# ALog-BottleLogger.net
KiCad netlist of a schematic drawn in EAGLE
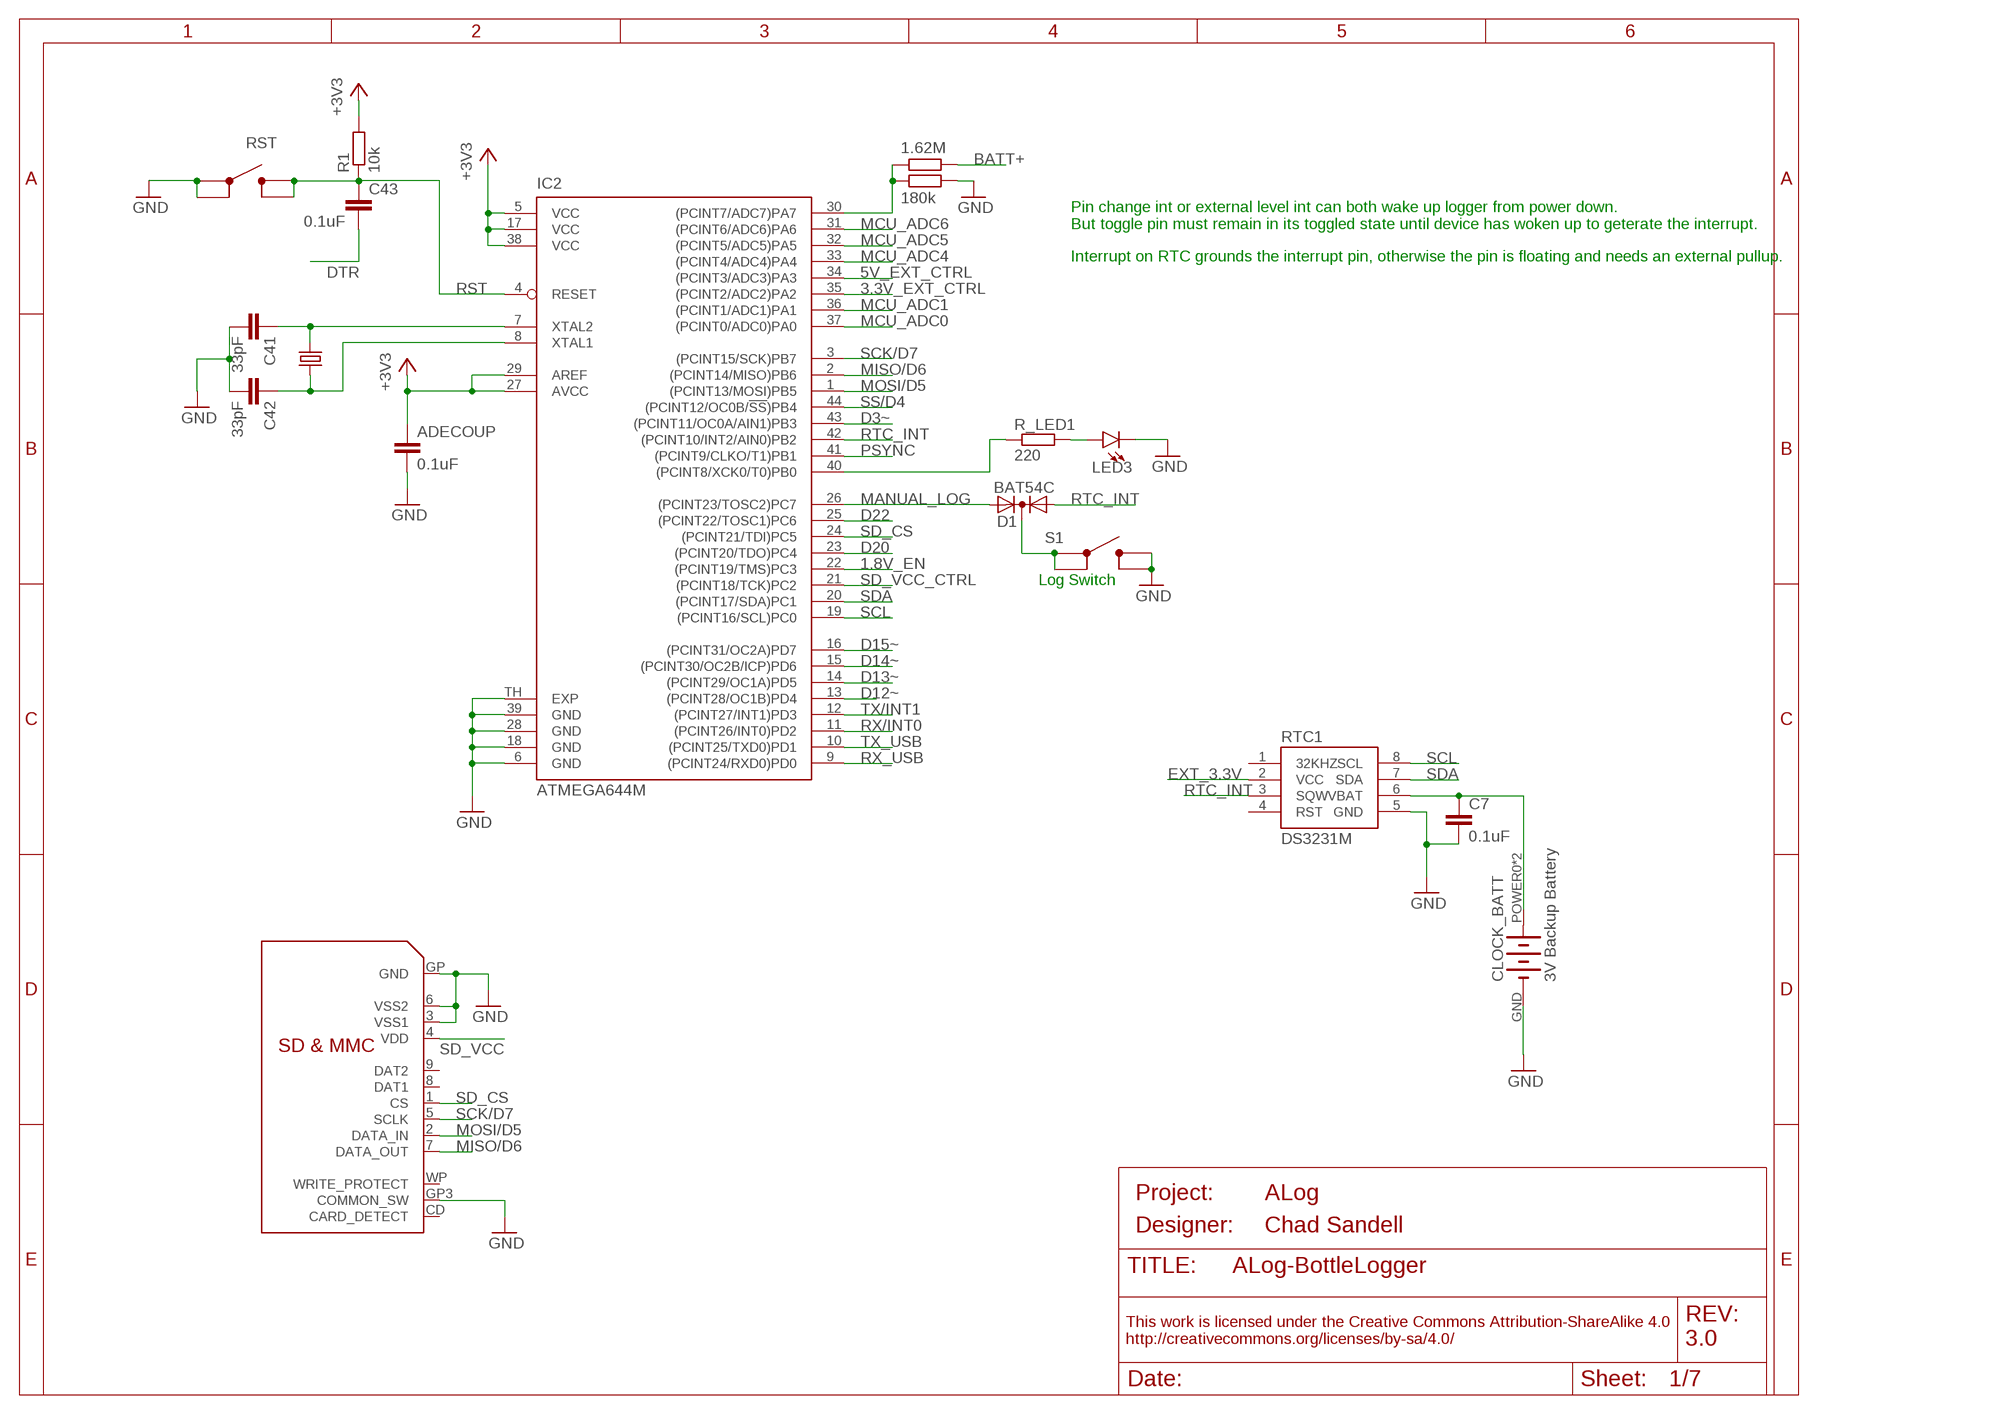
[diagram p0: schematic, sheet 1]
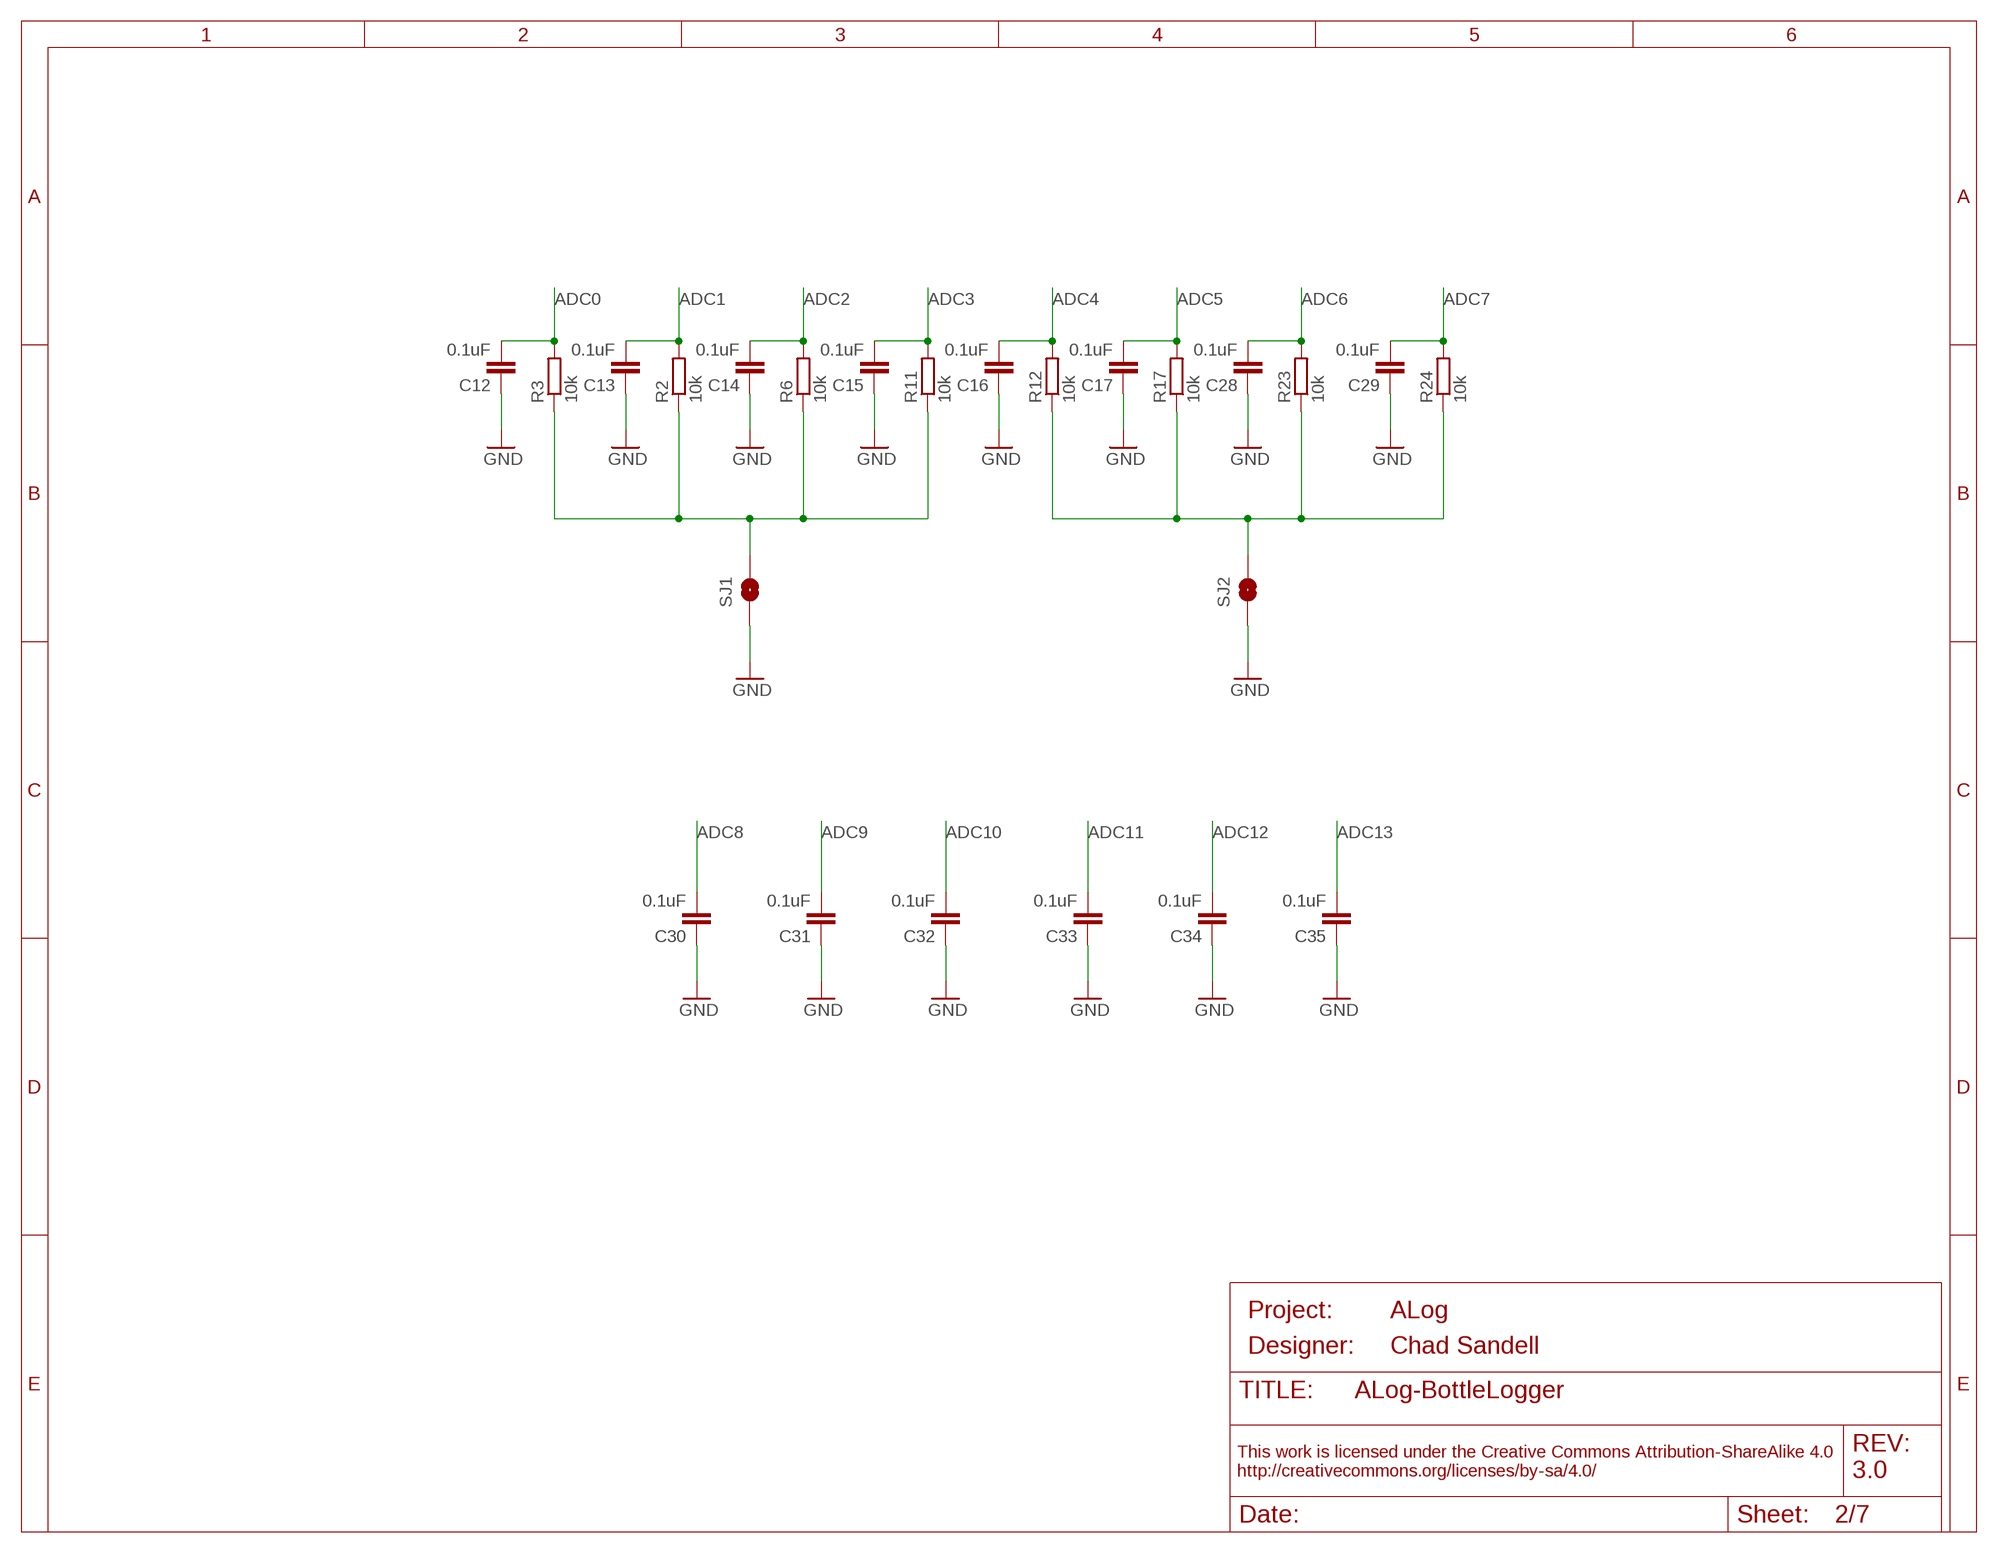
[diagram p1: schematic, sheet 2]
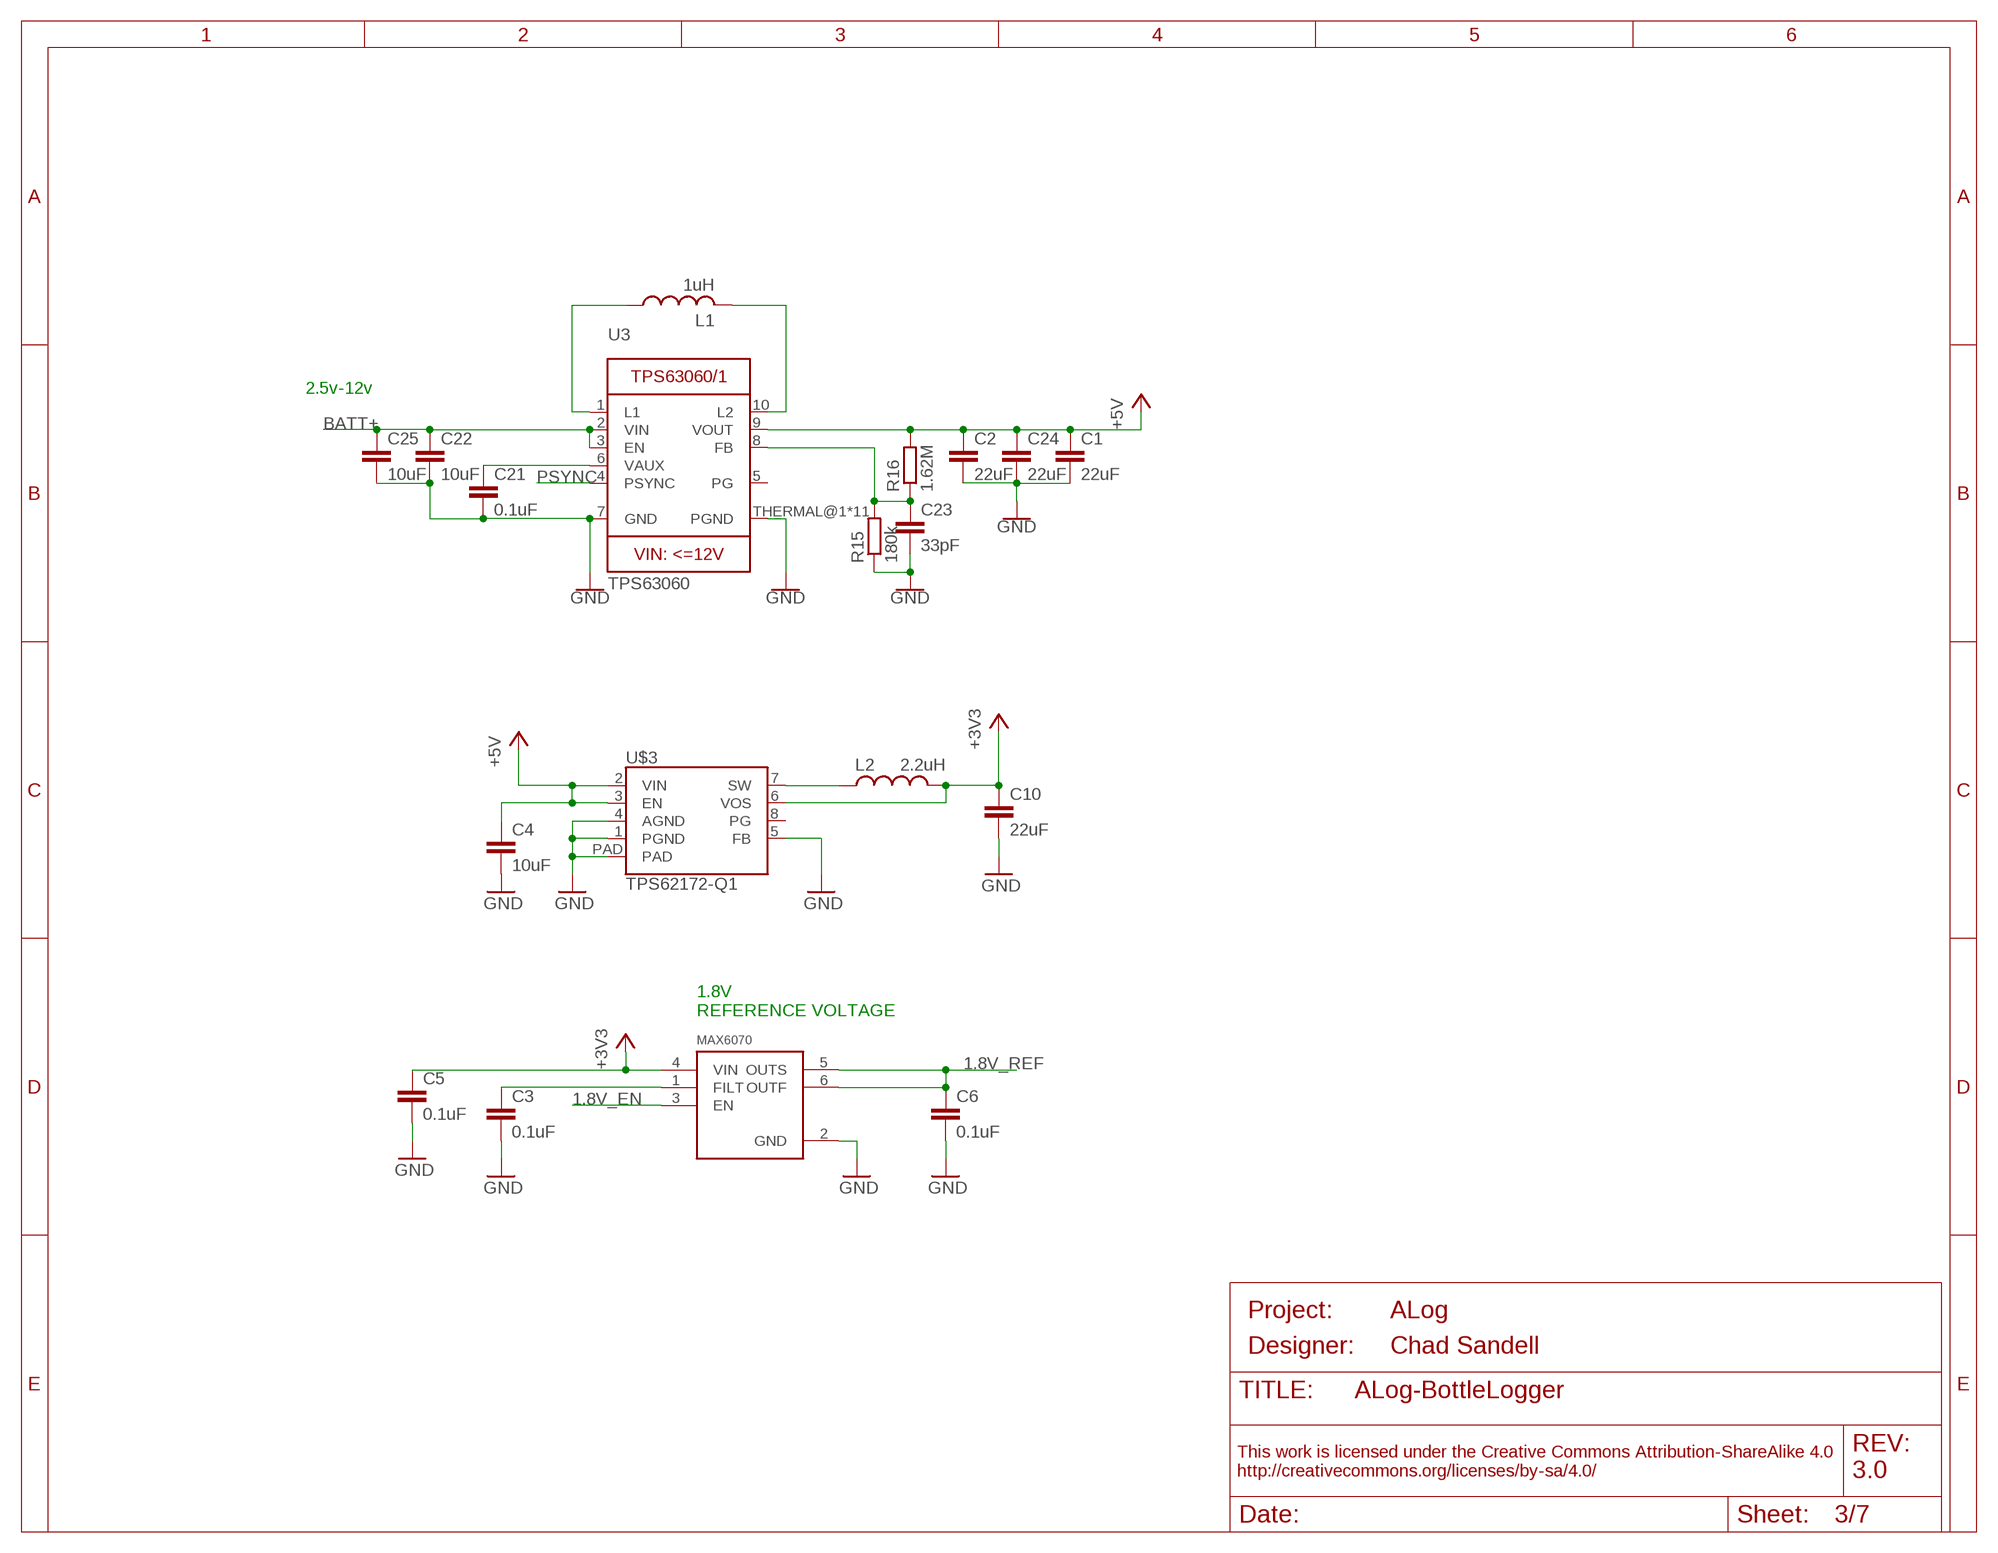
[diagram p2: schematic, sheet 3]
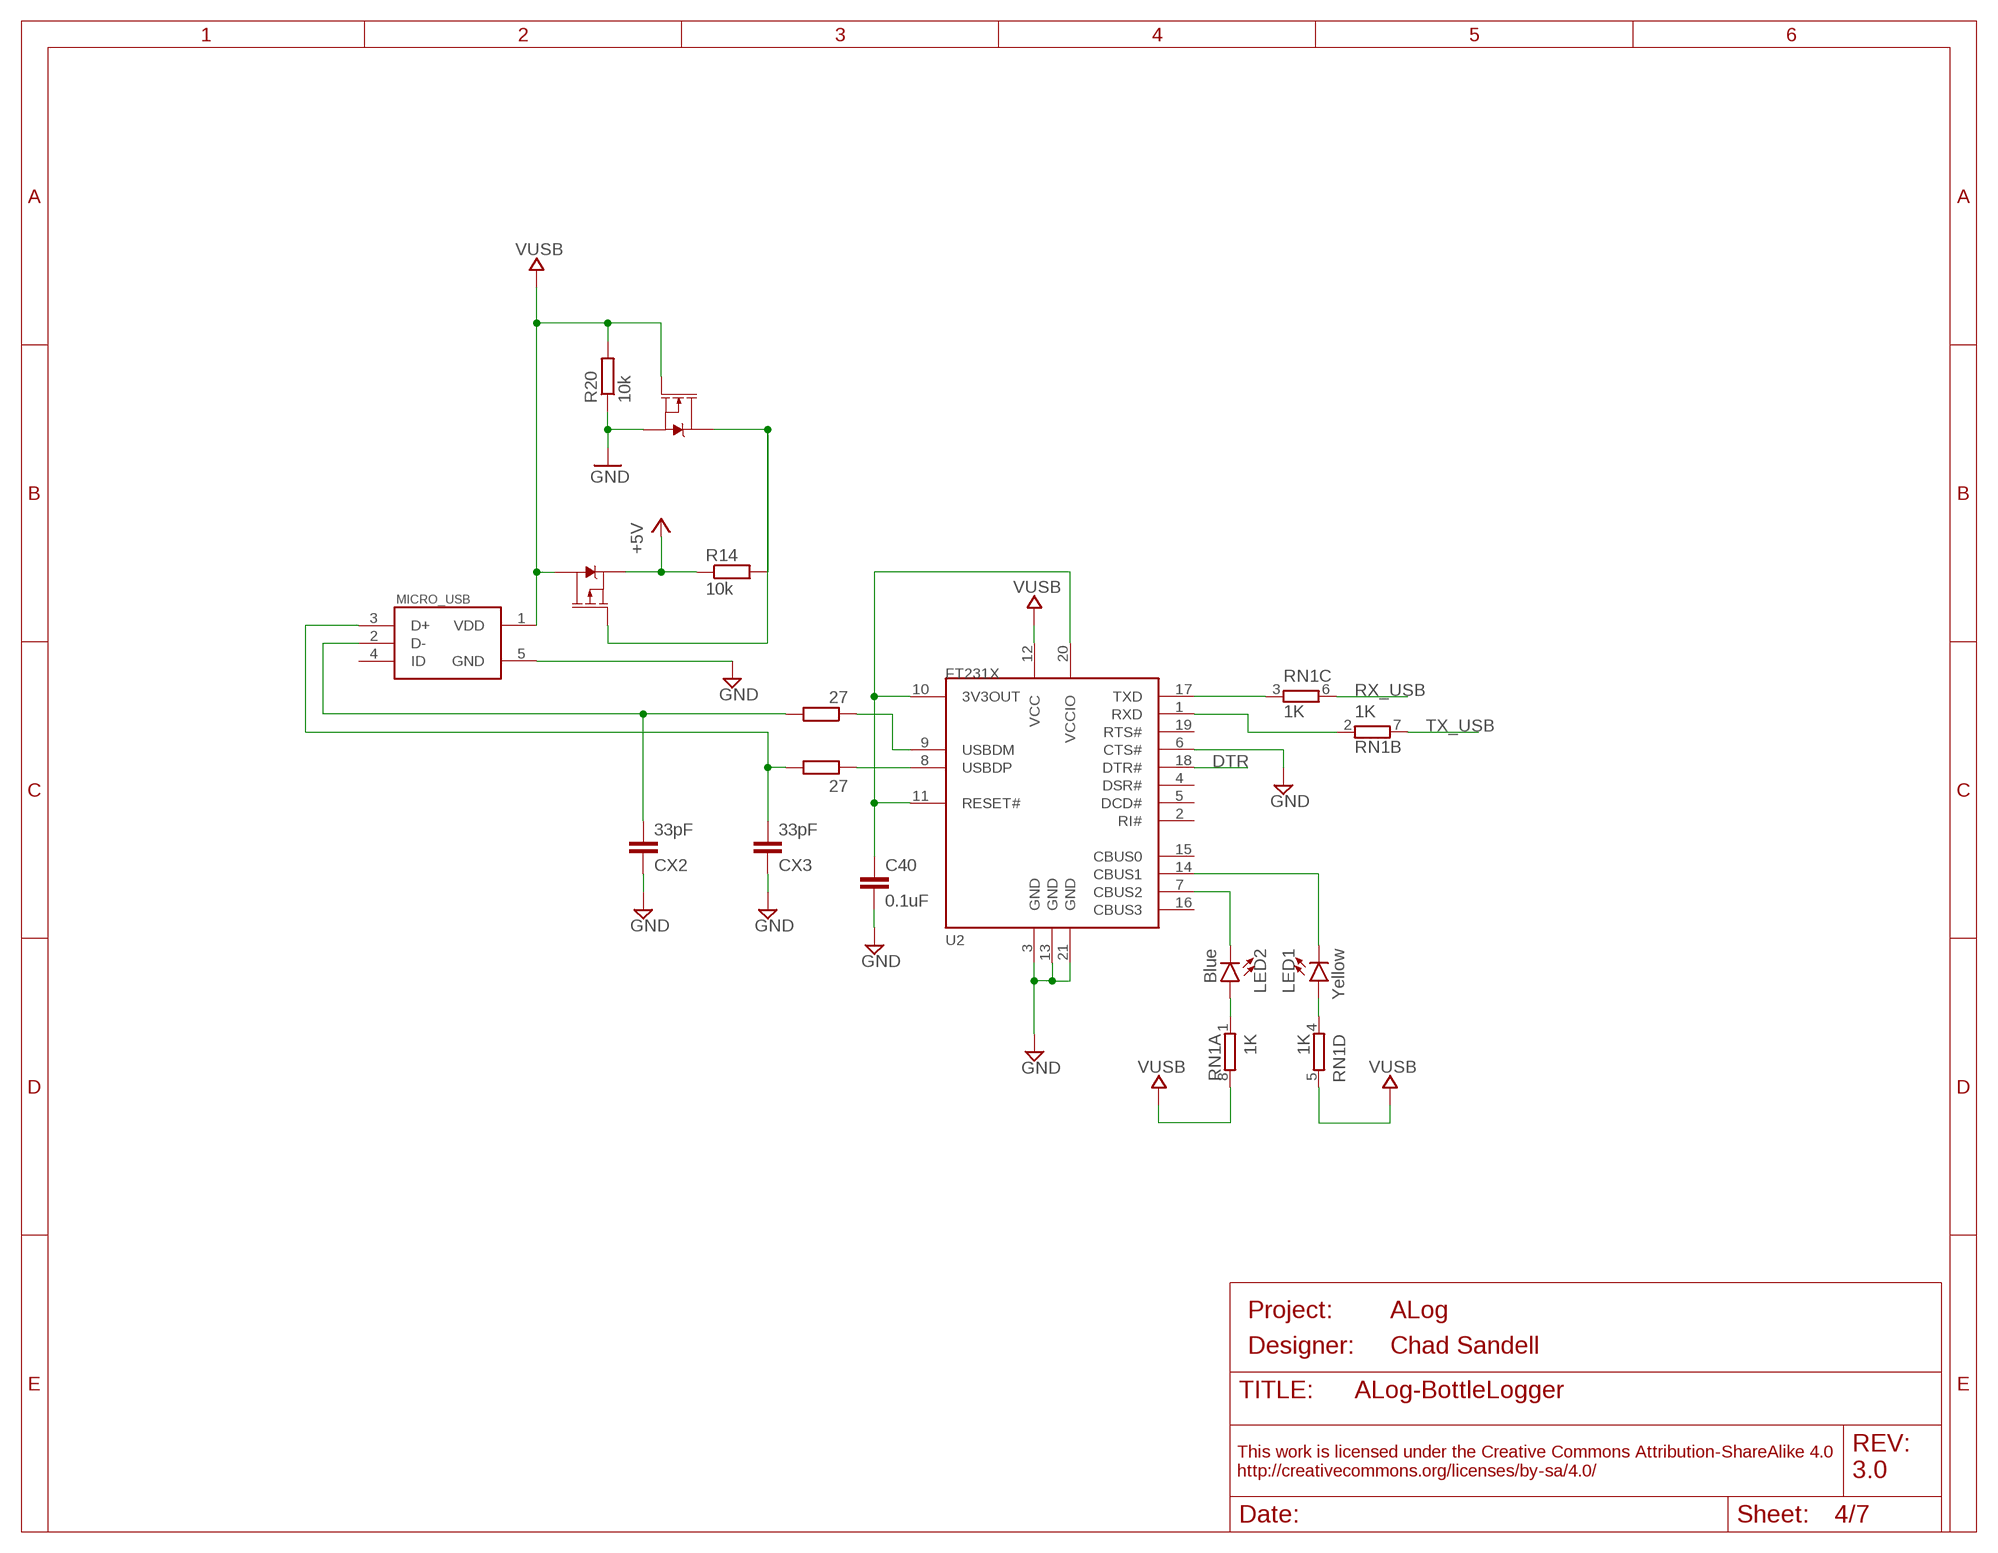
[diagram p3: schematic, sheet 4]
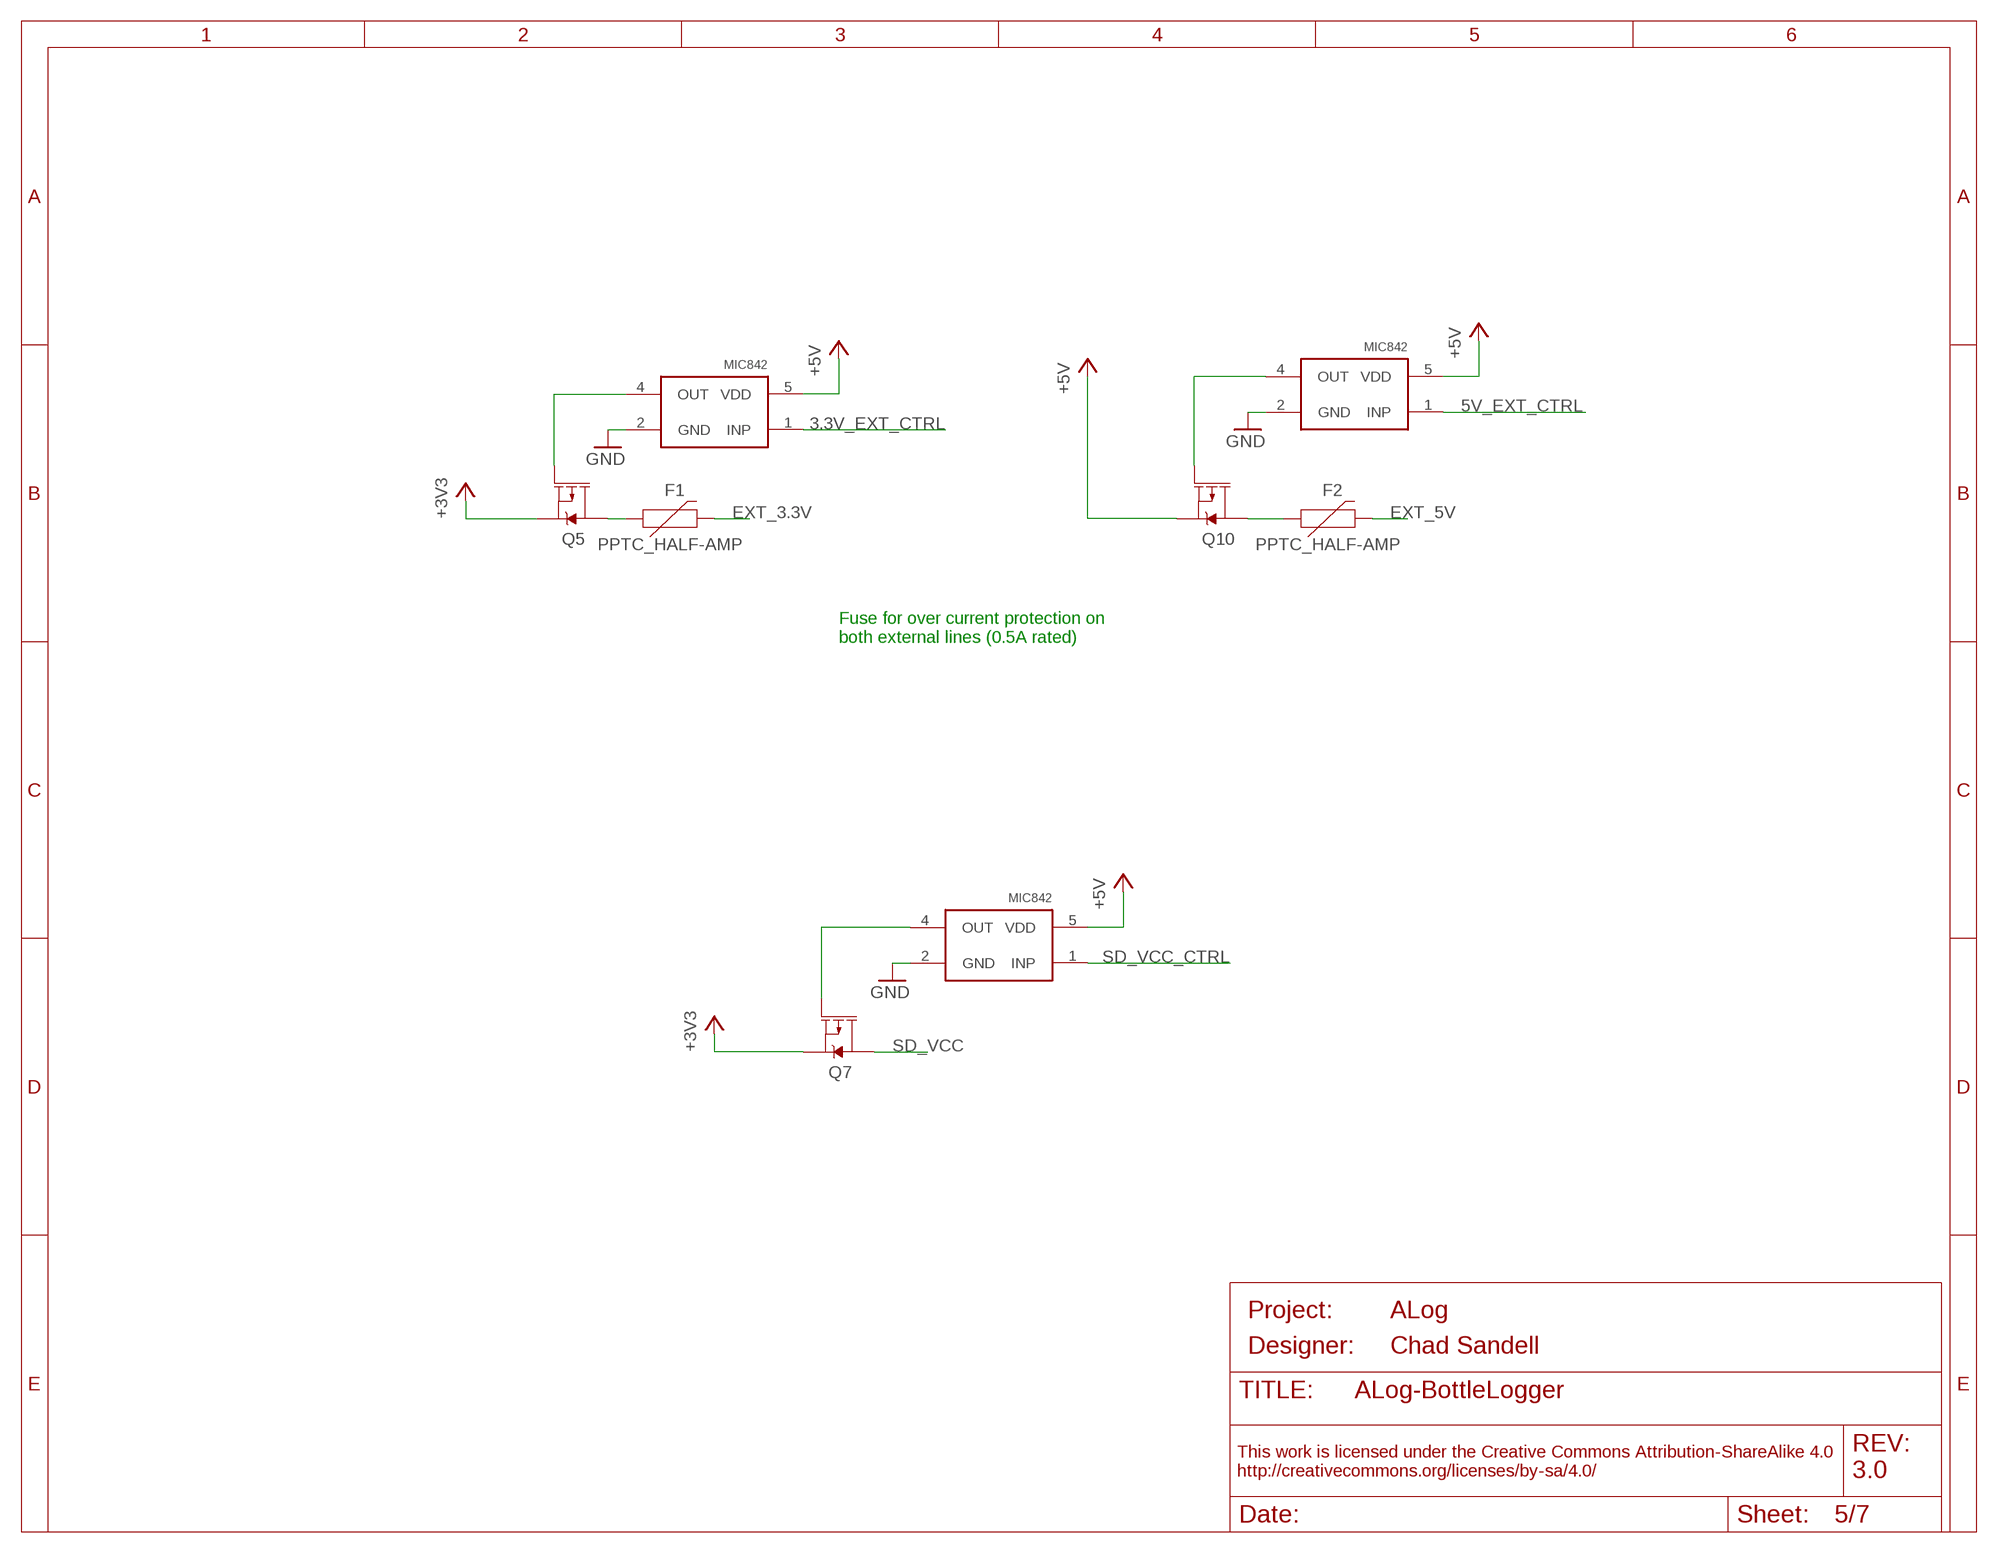
[diagram p4: schematic, sheet 5]
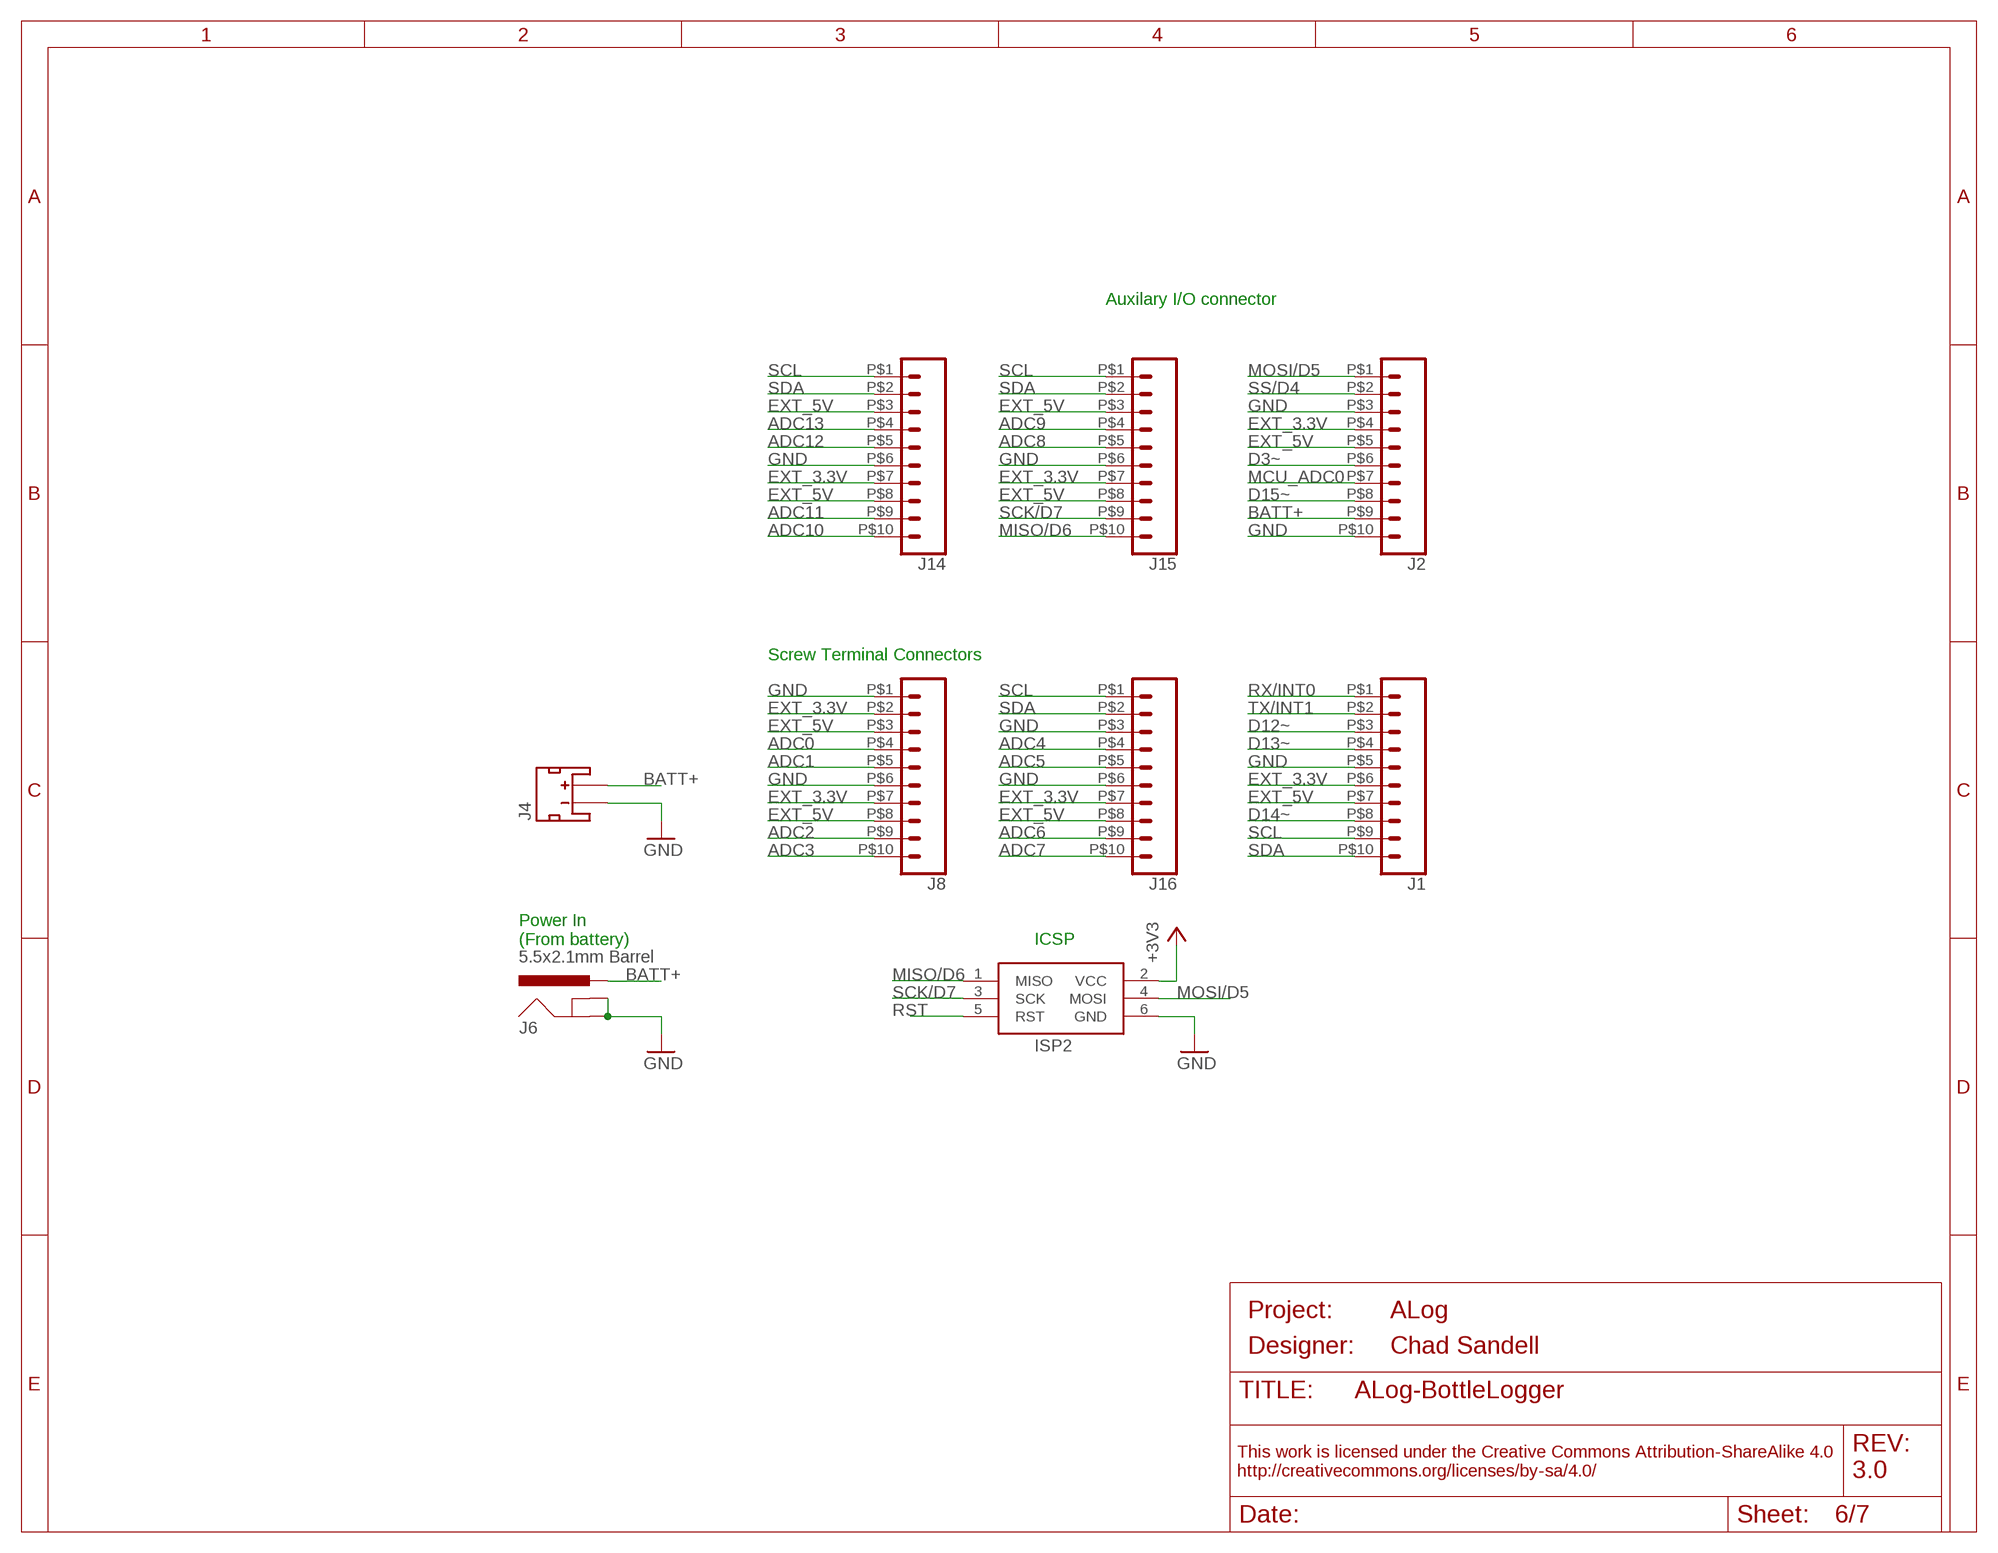
[diagram p5: schematic, sheet 6]
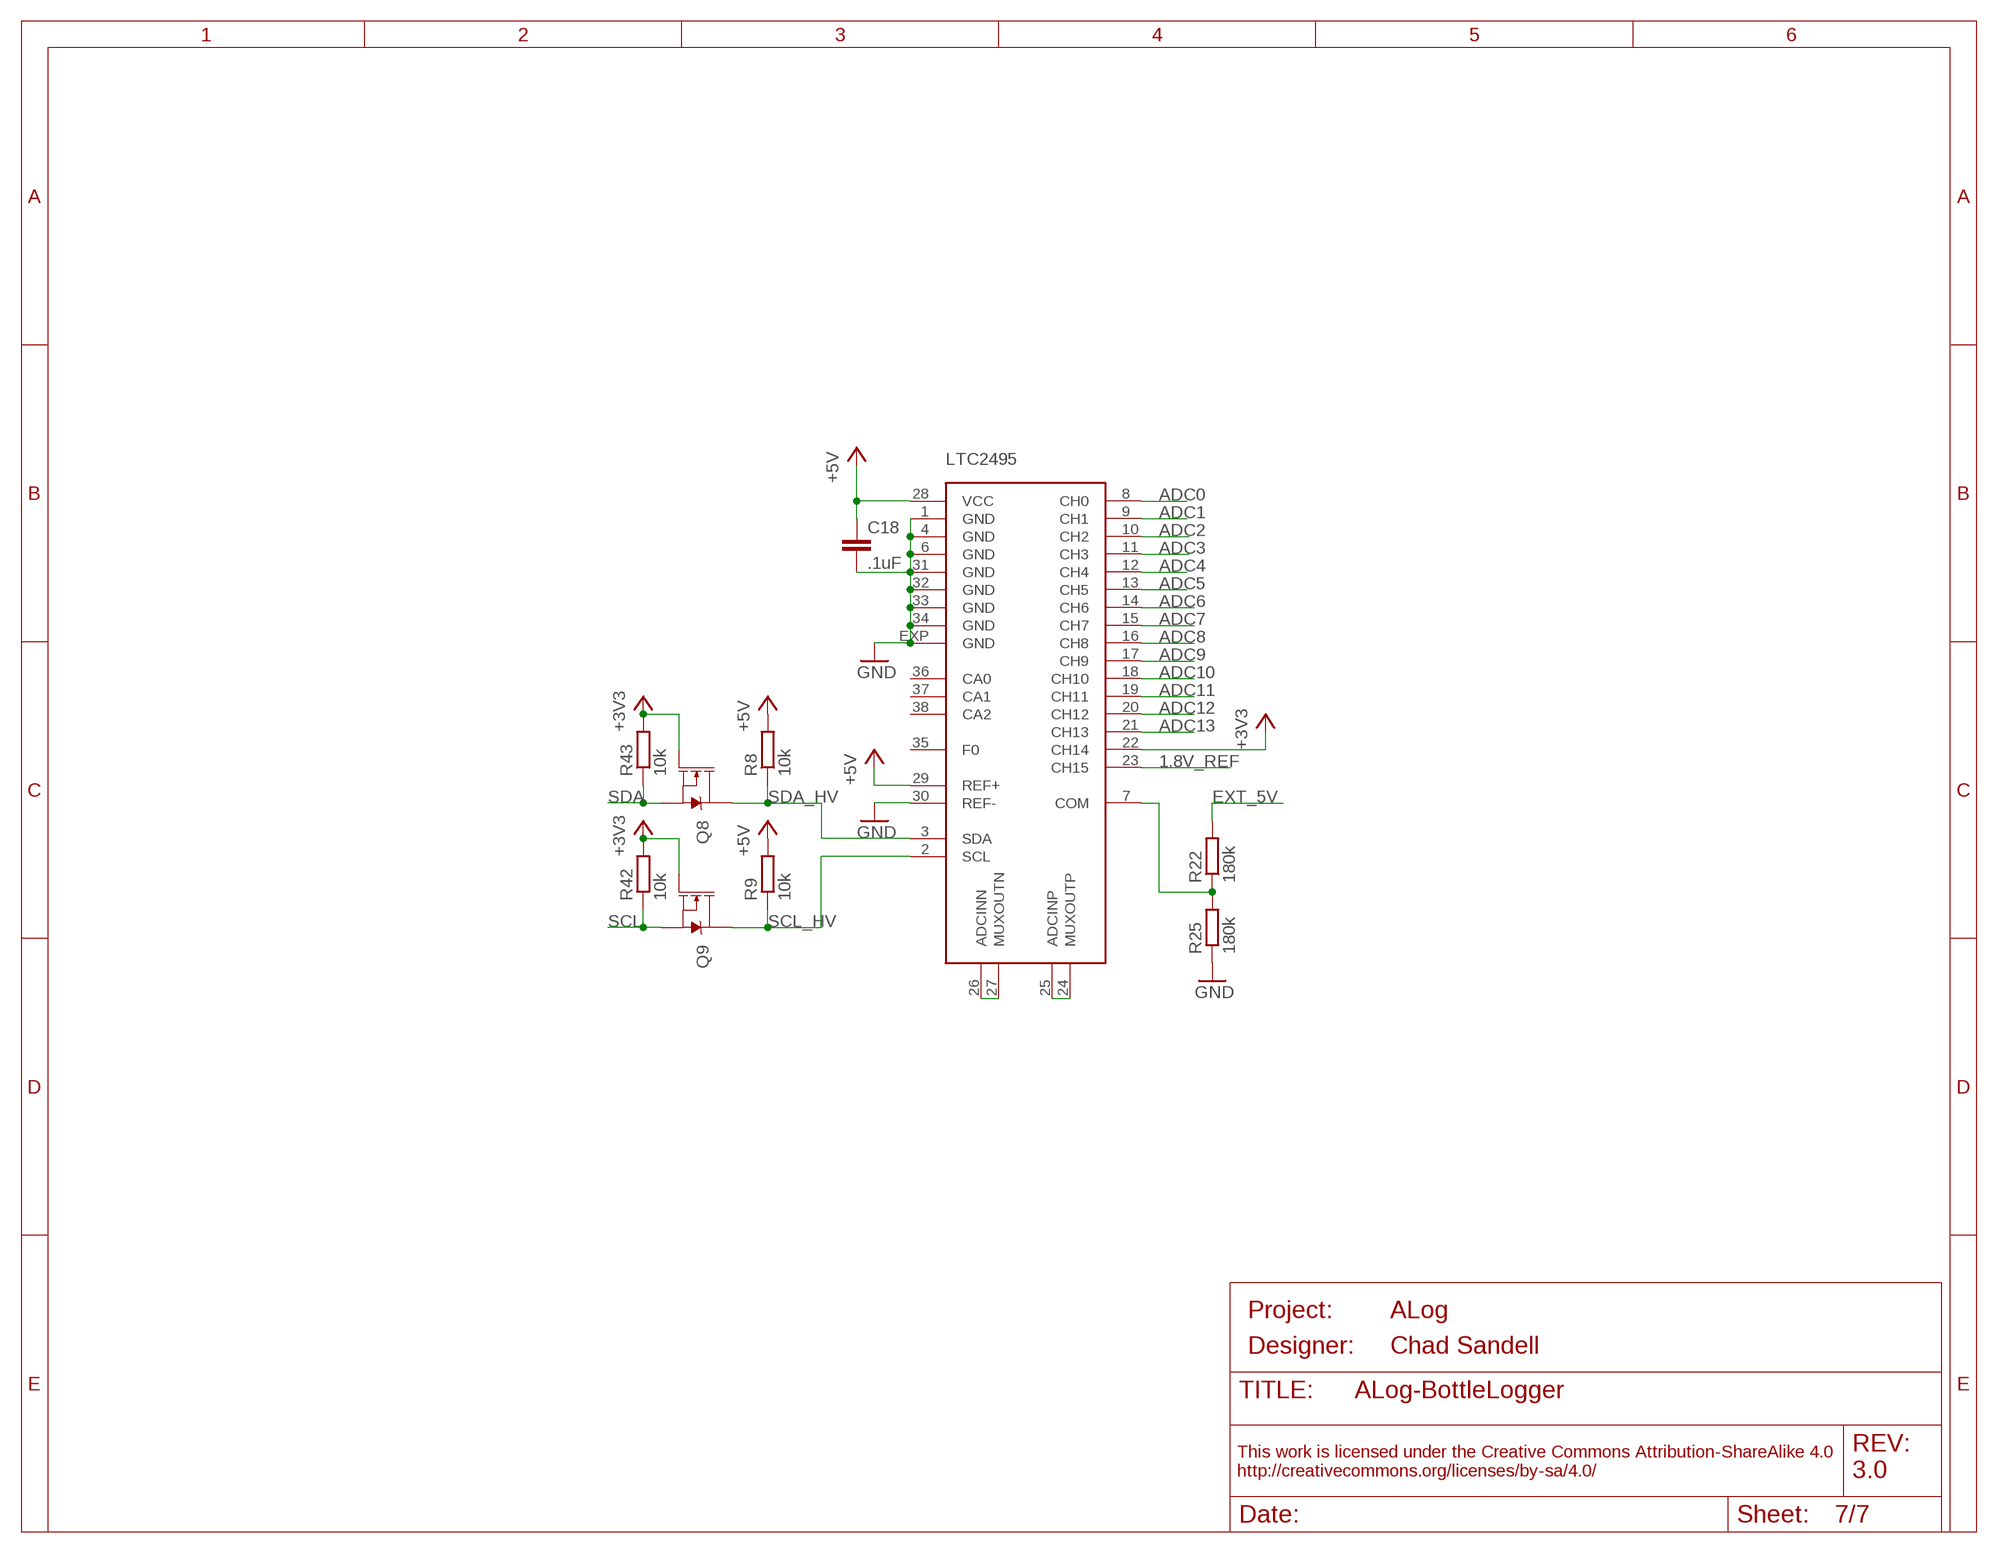
[diagram p6: schematic, sheet 7]

(export (version "E")
  (design (tool "Eeschema 10.0.6"))
  (components
    (comp (ref "F1")
      (value "PPTC_HALF-AMP")
      (footprint "eagle-import:1206")
      (fields (field (name "MF") "Bourns") (field (name "MPN") "MF-NSMF020-2"))
      (libsource (lib "eagle-import") (part "PPTC_HALF-AMP"))
    )
    (comp (ref "F2")
      (value "PPTC_HALF-AMP")
      (footprint "eagle-import:1206")
      (fields (field (name "MF") "Bourns") (field (name "MPN") "MF-NSMF020-2"))
      (libsource (lib "eagle-import") (part "bschulz_247464_PPTC_HALF-AMP"))
    )
    (comp (ref "Q5")
      (value "FDN360P")
      (footprint "eagle-import:SOT23-3")
      (fields (field (name "MF") "Fairchild"))
      (libsource (lib "eagle-import") (part "MOSFET_PCH-FDN360P"))
    )
    (comp (ref "Q7")
      (value "FDN360P")
      (footprint "eagle-import:SOT23-3")
      (fields (field (name "MF") "Fairchild"))
      (libsource (lib "eagle-import") (part "MOSFET_PCH-FDN360P"))
    )
    (comp (ref "Q10")
      (value "FDN360P")
      (footprint "eagle-import:SOT23-3")
      (fields (field (name "MF") "Fairchild"))
      (libsource (lib "eagle-import") (part "MOSFET_PCH-FDN360P"))
    )
    (comp (ref "U$1")
      (value "MIC842")
      (footprint "eagle-import:DCK_R-PDSO-G5")
      (libsource (lib "eagle-import") (part "MIC842"))
    )
    (comp (ref "U$12")
      (value "MIC842")
      (footprint "eagle-import:DCK_R-PDSO-G5")
      (libsource (lib "eagle-import") (part "MIC842"))
    )
    (comp (ref "U$16")
      (value "MIC842")
      (footprint "eagle-import:DCK_R-PDSO-G5")
      (libsource (lib "eagle-import") (part "MIC842"))
    )
    (comp (ref "ADECOUP")
      (value "0.1uF")
      (footprint "eagle-import:C0603")
      (fields (field (name "MF") "Samsung") (field (name "MPN") "CL10B104KO8NNNC"))
      (libsource (lib "eagle-import") (part "C-EUC06030.1UF"))
    )
    (comp (ref "C7")
      (value "0.1uF")
      (footprint "eagle-import:C0603")
      (fields (field (name "MF") "Samsung") (field (name "MPN") "CL10B104KO8NNNC"))
      (libsource (lib "eagle-import") (part "C-EUC06030.1UF"))
    )
    (comp (ref "C41")
      (value "33pF")
      (footprint "eagle-import:C0603")
      (libsource (lib "eagle-import") (part "rcl_334_C-EUC0603"))
    )
    (comp (ref "C42")
      (value "33pF")
      (footprint "eagle-import:C0603")
      (libsource (lib "eagle-import") (part "rcl_334_C-EUC0603"))
    )
    (comp (ref "C43")
      (value "0.1uF")
      (footprint "eagle-import:C0603")
      (fields (field (name "MF") "Samsung") (field (name "MPN") "CL10B104KO8NNNC"))
      (libsource (lib "eagle-import") (part "C-EUC06030.1UF"))
    )
    (comp (ref "CLOCK_BATT")
      (value "3V Backup Battery")
      (footprint "eagle-import:LINX_BAT-HLD-012-SMT")
      (libsource (lib "eagle-import") (part "LINX-BAT-HLD-012-SMT-OTL"))
    )
    (comp (ref "D1")
      (value "BAT54C")
      (footprint "eagle-import:SOT23C")
      (libsource (lib "eagle-import") (part "DIODE_AC-CA_"))
    )
    (comp (ref "IC2")
      (value "ATMEGA644M")
      (footprint "eagle-import:MLF44-TH")
      (fields (field (name "MF") "Atmel") (field (name "MPN") "ATMEGA644PA-MUR"))
      (libsource (lib "eagle-import") (part "ATMEGA644M"))
    )
    (comp (ref "LED3")
      (value "LED1206")
      (footprint "eagle-import:LED-1206")
      (libsource (lib "eagle-import") (part "LED1206"))
    )
    (comp (ref "Q3")
      (value "CRYSTALHC49UP")
      (footprint "eagle-import:HC49UP")
      (libsource (lib "eagle-import") (part "CRYSTALHC49UP"))
    )
    (comp (ref "R1")
      (value "10k")
      (footprint "eagle-import:R0603")
      (fields (field (name "MF") "Yageo") (field (name "MPN") "RC0603FR-0710KL"))
      (libsource (lib "eagle-import") (part "R-EU_R060310K"))
    )
    (comp (ref "R18")
      (value "1.62M")
      (footprint "eagle-import:R0603")
      (fields (field (name "MF") "Vishay Dale") (field (name "MPN") "CRCW06031M62FKEA"))
      (libsource (lib "eagle-import") (part "R-EU_R06031.62M"))
    )
    (comp (ref "R19")
      (value "180k")
      (footprint "eagle-import:R0603")
      (fields
        (field (name "MF") "Yageo")
        (field (name "MPN") "AC0603FR-07180KL")
        (field (name "VALUE_PART") "180K")
      )
      (libsource (lib "eagle-import") (part "R-EU_R0603180K"))
    )
    (comp (ref "RTC1")
      (value "DS3231M")
      (footprint "eagle-import:SO08")
      (fields (field (name "MF") "Maxim") (field (name "MPN") "DS3231MZ+"))
      (libsource (lib "eagle-import") (part "DS3231M"))
    )
    (comp (ref "R_LED1")
      (value "220")
      (footprint "eagle-import:R0603")
      (libsource (lib "eagle-import") (part "R-EU_R0603"))
    )
    (comp (ref "S1")
      (value "SWITCHC&K_400GF")
      (footprint "eagle-import:SWITCH_4.2X3.2")
      (fields (field (name "MF") "C&K") (field (name "MPN") "PTS810 SJG 250 SMTR LFS"))
      (libsource (lib "eagle-import") (part "SWITCHC&K_400GF"))
    )
    (comp (ref "SD")
      (value "SDMMC06132")
      (footprint "eagle-import:06132")
      (libsource (lib "eagle-import") (part "SDMMC06132"))
    )
    (comp (ref "U$4")
      (value "SWITCHC&K_400GF")
      (footprint "eagle-import:SWITCH_4.2X3.2")
      (fields (field (name "MF") "C&K") (field (name "MPN") "PTS810 SJG 250 SMTR LFS"))
      (libsource (lib "eagle-import") (part "SWITCHC&K_400GF"))
    )
    (comp (ref "ISP2")
      (value "AVRISP-6")
      (footprint "eagle-import:AVRISP")
      (libsource (lib "eagle-import") (part "AVRISP-6"))
    )
    (comp (ref "J1")
      (value "CONN_103.5MM")
      (footprint "eagle-import:1X10_3.5MM_SCREW")
      (libsource (lib "eagle-import") (part "CONN_103.5MM"))
    )
    (comp (ref "J2")
      (value "CONN_103.5MM")
      (footprint "eagle-import:1X10_3.5MM_SCREW")
      (libsource (lib "eagle-import") (part "CONN_103.5MM"))
    )
    (comp (ref "J4")
      (value "JST_2MM_MALE")
      (footprint "eagle-import:JST-2-SMD")
      (fields (field (name "MF") "JST") (field (name "MPN") "S2B-PH-SM4-TB(LF)(SN)"))
      (libsource (lib "eagle-import") (part "JST_2MM_MALE"))
    )
    (comp (ref "J6")
      (value "5.5x2.1mm Barrel")
      (footprint "eagle-import:POWER_JACK_SMD")
      (fields (field (name "MF") "Wurth") (field (name "MPN") "694106106102"))
      (libsource (lib "eagle-import") (part "POWER_JACKSMD"))
    )
    (comp (ref "J8")
      (value "CONN_103.5MM")
      (footprint "eagle-import:1X10_3.5MM_SCREW")
      (libsource (lib "eagle-import") (part "CONN_103.5MM"))
    )
    (comp (ref "J14")
      (value "CONN_103.5MM")
      (footprint "eagle-import:1X10_3.5MM_SCREW")
      (libsource (lib "eagle-import") (part "CONN_103.5MM"))
    )
    (comp (ref "J15")
      (value "CONN_103.5MM")
      (footprint "eagle-import:1X10_3.5MM_SCREW")
      (libsource (lib "eagle-import") (part "CONN_103.5MM"))
    )
    (comp (ref "J16")
      (value "CONN_103.5MM")
      (footprint "eagle-import:1X10_3.5MM_SCREW")
      (libsource (lib "eagle-import") (part "CONN_103.5MM"))
    )
    (comp (ref "C1")
      (value "22uF")
      (footprint "eagle-import:C0805")
      (fields (field (name "MF") "Samsung") (field (name "MPN") "CL21A226KQCLRNC"))
      (libsource (lib "eagle-import") (part "C-EUC080522UF"))
    )
    (comp (ref "C2")
      (value "22uF")
      (footprint "eagle-import:C0805")
      (fields (field (name "MF") "Samsung") (field (name "MPN") "CL21A226KQCLRNC"))
      (libsource (lib "eagle-import") (part "C-EUC080522UF"))
    )
    (comp (ref "C3")
      (value "0.1uF")
      (footprint "eagle-import:C0603")
      (fields (field (name "MF") "Samsung") (field (name "MPN") "CL10B104KO8NNNC"))
      (libsource (lib "eagle-import") (part "C-EUC06030.1UF"))
    )
    (comp (ref "C4")
      (value "10uF")
      (footprint "eagle-import:C0805")
      (fields (field (name "MF") "Samsung") (field (name "MPN") "CL21A106KQCLRNC"))
      (libsource (lib "eagle-import") (part "C-EUC080510UF"))
    )
    (comp (ref "C5")
      (value "0.1uF")
      (footprint "eagle-import:C0603")
      (libsource (lib "eagle-import") (part "rcl_334_C-EUC0603"))
    )
    (comp (ref "C6")
      (value "0.1uF")
      (footprint "eagle-import:C0603")
      (libsource (lib "eagle-import") (part "rcl_334_C-EUC0603"))
    )
    (comp (ref "C10")
      (value "22uF")
      (footprint "eagle-import:C0805")
      (fields (field (name "MF") "Samsung") (field (name "MPN") "CL21A226KQCLRNC"))
      (libsource (lib "eagle-import") (part "C-EUC080522UF"))
    )
    (comp (ref "C21")
      (value "0.1uF")
      (footprint "eagle-import:C0603")
      (libsource (lib "eagle-import") (part "rcl_334_C-EUC0603"))
    )
    (comp (ref "C22")
      (value "10uF")
      (footprint "eagle-import:C0805")
      (fields (field (name "MF") "Samsung") (field (name "MPN") "CL21A106KQCLRNC"))
      (libsource (lib "eagle-import") (part "C-EUC080510UF"))
    )
    (comp (ref "C23")
      (value "33pF")
      (footprint "eagle-import:C0603")
      (libsource (lib "eagle-import") (part "rcl_334_C-EUC0603"))
    )
    (comp (ref "C24")
      (value "22uF")
      (footprint "eagle-import:C0805")
      (fields (field (name "MF") "Samsung") (field (name "MPN") "CL21A226KQCLRNC"))
      (libsource (lib "eagle-import") (part "C-EUC080522UF"))
    )
    (comp (ref "C25")
      (value "10uF")
      (footprint "eagle-import:C0805")
      (fields (field (name "MF") "Samsung") (field (name "MPN") "CL21A106KQCLRNC"))
      (libsource (lib "eagle-import") (part "C-EUC080510UF"))
    )
    (comp (ref "L1")
      (value "1uH")
      (footprint "eagle-import:WE-MAIA(4.1X4.1)")
      (libsource (lib "eagle-import") (part "WE-MAIA(INDUCTOR)"))
    )
    (comp (ref "L2")
      (value "2.2uH")
      (footprint "eagle-import:0806")
      (libsource (lib "eagle-import") (part "INDUCTOR0806"))
    )
    (comp (ref "R15")
      (value "180k")
      (footprint "eagle-import:R0603")
      (fields
        (field (name "MF") "Yageo")
        (field (name "MPN") "AC0603FR-07180KL")
        (field (name "VALUE_PART") "180K")
      )
      (libsource (lib "eagle-import") (part "R-EU_R0603180K"))
    )
    (comp (ref "R16")
      (value "1.62M")
      (footprint "eagle-import:R0603")
      (fields (field (name "MF") "Vishay Dale") (field (name "MPN") "CRCW06031M62FKEA"))
      (libsource (lib "eagle-import") (part "R-EU_R06031.62M"))
    )
    (comp (ref "U$2")
      (value "MAX6070AAUT18")
      (footprint "eagle-import:SOT23-6L")
      (fields (field (name "MF") "Maxim") (field (name "MPN") "MAX6070BAUT18+T"))
      (libsource (lib "eagle-import") (part "MAX6070AAUT18"))
    )
    (comp (ref "U$3")
      (value "TPS62172-Q1")
      (footprint "eagle-import:WSON-8-PAD")
      (fields (field (name "MF") "TI") (field (name "MPN") "TPS62172QDSGRQ1"))
      (libsource (lib "eagle-import") (part "TPS6217-Q12"))
    )
    (comp (ref "U3")
      (value "TPS63060")
      (footprint "eagle-import:PWSON-N10")
      (fields (field (name "MF") "TI") (field (name "MPN") "TPS63060DSCR"))
      (libsource (lib "eagle-import") (part "TPS63060"))
    )
    (comp (ref "C40")
      (value "0.1uF")
      (footprint "eagle-import:C0603")
      (fields (field (name "MF") "Samsung") (field (name "MPN") "CL10B104KO8NNNC"))
      (libsource (lib "eagle-import") (part "C-EUC06030.1UF"))
    )
    (comp (ref "CX2")
      (value "33pF")
      (footprint "eagle-import:C0603")
      (libsource (lib "eagle-import") (part "resistor_348_C-EUC0603"))
    )
    (comp (ref "CX3")
      (value "33pF")
      (footprint "eagle-import:C0603")
      (libsource (lib "eagle-import") (part "resistor_348_C-EUC0603"))
    )
    (comp (ref "D+")
      (value "27")
      (footprint "eagle-import:R0603")
      (fields (field (name "MF") "Yageo") (field (name "MPN") "RC0603FR-0727RL"))
      (libsource (lib "eagle-import") (part "R-EU_R060327"))
    )
    (comp (ref "D-")
      (value "27")
      (footprint "eagle-import:R0603")
      (fields (field (name "MF") "Yageo") (field (name "MPN") "RC0603FR-0727RL"))
      (libsource (lib "eagle-import") (part "R-EU_R060327"))
    )
    (comp (ref "LED1")
      (value "Yellow")
      (footprint "eagle-import:LED-0603")
      (libsource (lib "eagle-import") (part "LED0603"))
    )
    (comp (ref "LED2")
      (value "Blue")
      (footprint "eagle-import:LED-0603")
      (libsource (lib "eagle-import") (part "LED0603"))
    )
    (comp (ref "MICRO_USB")
      (value "MICRO_USB_LONGPADS")
      (footprint "eagle-import:10118194-0001LF_10118194-0001LF_LONGER_PADS")
      (fields (field (name "MF") "Amphenol") (field (name "MPN") "10118194-0001LF"))
      (libsource (lib "eagle-import") (part "MICRO_USB_LONGPADS"))
    )
    (comp (ref "Q11")
      (value "310mA/60V/1.6Ω")
      (footprint "eagle-import:SOT323")
      (libsource (lib "eagle-import") (part "bschulz_247464_MOSFET-NCH-2N7002PW"))
    )
    (comp (ref "Q12")
      (value "FDN360P")
      (footprint "eagle-import:SOT23-3")
      (fields (field (name "MF") "Fairchild"))
      (libsource (lib "eagle-import") (part "MOSFET_PCH-FDN360P"))
    )
    (comp (ref "R14")
      (value "10k")
      (footprint "eagle-import:R0603")
      (libsource (lib "eagle-import") (part "rcl_334_R-EU_R0603"))
    )
    (comp (ref "R20")
      (value "10k")
      (footprint "eagle-import:R0603")
      (libsource (lib "eagle-import") (part "rcl_334_R-EU_R0603"))
    )
    (comp (ref "RN1")
      (value "1K")
      (footprint "eagle-import:0603-ARC")
      (libsource (lib "eagle-import") (part "4R-N0603-ARC"))
    )
    (comp (ref "U2")
      (value "FT231X-Q")
      (footprint "eagle-import:QFN20")
      (fields (field (name "MF") "FTDI") (field (name "MPN") "FT231XQ-R"))
      (libsource (lib "eagle-import") (part "FT231X-Q"))
    )
    (comp (ref "C12")
      (value "0.1uF")
      (footprint "eagle-import:C0603")
      (libsource (lib "eagle-import") (part "rcl_334_C-EUC0603"))
    )
    (comp (ref "C13")
      (value "0.1uF")
      (footprint "eagle-import:C0603")
      (fields (field (name "MF") "Samsung") (field (name "MPN") "CL10B104KO8NNNC"))
      (libsource (lib "eagle-import") (part "C-EUC06030.1UF"))
    )
    (comp (ref "C14")
      (value "0.1uF")
      (footprint "eagle-import:C0603")
      (libsource (lib "eagle-import") (part "rcl_334_C-EUC0603"))
    )
    (comp (ref "C15")
      (value "0.1uF")
      (footprint "eagle-import:C0603")
      (fields (field (name "MF") "Samsung") (field (name "MPN") "CL10B104KO8NNNC"))
      (libsource (lib "eagle-import") (part "C-EUC06030.1UF"))
    )
    (comp (ref "C16")
      (value "0.1uF")
      (footprint "eagle-import:C0603")
      (fields (field (name "MF") "Samsung") (field (name "MPN") "CL10B104KO8NNNC"))
      (libsource (lib "eagle-import") (part "C-EUC06030.1UF"))
    )
    (comp (ref "C17")
      (value "0.1uF")
      (footprint "eagle-import:C0603")
      (fields (field (name "MF") "Samsung") (field (name "MPN") "CL10B104KO8NNNC"))
      (libsource (lib "eagle-import") (part "C-EUC06030.1UF"))
    )
    (comp (ref "C28")
      (value "0.1uF")
      (footprint "eagle-import:C0603")
      (fields (field (name "MF") "Samsung") (field (name "MPN") "CL10B104KO8NNNC"))
      (libsource (lib "eagle-import") (part "C-EUC06030.1UF"))
    )
    (comp (ref "C29")
      (value "0.1uF")
      (footprint "eagle-import:C0603")
      (fields (field (name "MF") "Samsung") (field (name "MPN") "CL10B104KO8NNNC"))
      (libsource (lib "eagle-import") (part "C-EUC06030.1UF"))
    )
    (comp (ref "C30")
      (value "0.1uF")
      (footprint "eagle-import:C0603")
      (fields (field (name "MF") "Samsung") (field (name "MPN") "CL10B104KO8NNNC"))
      (libsource (lib "eagle-import") (part "C-EUC06030.1UF"))
    )
    (comp (ref "C31")
      (value "0.1uF")
      (footprint "eagle-import:C0603")
      (fields (field (name "MF") "Samsung") (field (name "MPN") "CL10B104KO8NNNC"))
      (libsource (lib "eagle-import") (part "C-EUC06030.1UF"))
    )
    (comp (ref "C32")
      (value "0.1uF")
      (footprint "eagle-import:C0603")
      (fields (field (name "MF") "Samsung") (field (name "MPN") "CL10B104KO8NNNC"))
      (libsource (lib "eagle-import") (part "C-EUC06030.1UF"))
    )
    (comp (ref "C33")
      (value "0.1uF")
      (footprint "eagle-import:C0603")
      (fields (field (name "MF") "Samsung") (field (name "MPN") "CL10B104KO8NNNC"))
      (libsource (lib "eagle-import") (part "C-EUC06030.1UF"))
    )
    (comp (ref "C34")
      (value "0.1uF")
      (footprint "eagle-import:C0603")
      (fields (field (name "MF") "Samsung") (field (name "MPN") "CL10B104KO8NNNC"))
      (libsource (lib "eagle-import") (part "C-EUC06030.1UF"))
    )
    (comp (ref "C35")
      (value "0.1uF")
      (footprint "eagle-import:C0603")
      (fields (field (name "MF") "Samsung") (field (name "MPN") "CL10B104KO8NNNC"))
      (libsource (lib "eagle-import") (part "C-EUC06030.1UF"))
    )
    (comp (ref "R2")
      (value "10k")
      (footprint "eagle-import:R0603")
      (fields (field (name "MF") "Yageo") (field (name "MPN") "RC0603FR-0710KL"))
      (libsource (lib "eagle-import") (part "R-EU_R060310K"))
    )
    (comp (ref "R3")
      (value "10k")
      (footprint "eagle-import:R0603")
      (fields (field (name "MF") "Yageo") (field (name "MPN") "RC0603FR-0710KL"))
      (libsource (lib "eagle-import") (part "R-EU_R060310K"))
    )
    (comp (ref "R6")
      (value "10k")
      (footprint "eagle-import:R0603")
      (fields (field (name "MF") "Yageo") (field (name "MPN") "RC0603FR-0710KL"))
      (libsource (lib "eagle-import") (part "R-EU_R060310K"))
    )
    (comp (ref "R11")
      (value "10k")
      (footprint "eagle-import:R0603")
      (fields (field (name "MF") "Yageo") (field (name "MPN") "RC0603FR-0710KL"))
      (libsource (lib "eagle-import") (part "R-EU_R060310K"))
    )
    (comp (ref "R12")
      (value "10k")
      (footprint "eagle-import:R0603")
      (fields (field (name "MF") "Yageo") (field (name "MPN") "RC0603FR-0710KL"))
      (libsource (lib "eagle-import") (part "R-EU_R060310K"))
    )
    (comp (ref "R17")
      (value "10k")
      (footprint "eagle-import:R0603")
      (fields (field (name "MF") "Yageo") (field (name "MPN") "RC0603FR-0710KL"))
      (libsource (lib "eagle-import") (part "R-EU_R060310K"))
    )
    (comp (ref "R23")
      (value "10k")
      (footprint "eagle-import:R0603")
      (fields (field (name "MF") "Yageo") (field (name "MPN") "RC0603FR-0710KL"))
      (libsource (lib "eagle-import") (part "R-EU_R060310K"))
    )
    (comp (ref "R24")
      (value "10k")
      (footprint "eagle-import:R0603")
      (fields (field (name "MF") "Yageo") (field (name "MPN") "RC0603FR-0710KL"))
      (libsource (lib "eagle-import") (part "R-EU_R060310K"))
    )
    (comp (ref "SJ1")
      (value "SOLDERJUMPER-OLDTRACE")
      (footprint "eagle-import:SJ_2S-TRACE")
      (libsource (lib "eagle-import") (part "SOLDERJUMPER-OLDTRACE"))
    )
    (comp (ref "SJ2")
      (value "SOLDERJUMPER-OLDTRACE")
      (footprint "eagle-import:SJ_2S-TRACE")
      (libsource (lib "eagle-import") (part "SOLDERJUMPER-OLDTRACE"))
    )
    (comp (ref "C18")
      (value ".1uF")
      (footprint "eagle-import:C0603")
      (fields (field (name "MF") "Samsung") (field (name "MPN") "CL10B104KO8NNNC"))
      (libsource (lib "eagle-import") (part "C-EUC06030.1UF"))
    )
    (comp (ref "Q8")
      (value "310mA/60V/1.6Ω")
      (footprint "eagle-import:SOT323")
      (libsource (lib "eagle-import") (part "bschulz_247464_MOSFET-NCH-2N7002PW"))
    )
    (comp (ref "Q9")
      (value "2N7002")
      (footprint "eagle-import:SOT323")
      (fields (field (name "MF") "Diodes Incorporated") (field (name "MPN") "2N7002W-7-F"))
      (libsource (lib "eagle-import") (part "MOSFET-NCH-2N7002PW"))
    )
    (comp (ref "R8")
      (value "10k")
      (footprint "eagle-import:R0603")
      (fields (field (name "MF") "Yageo") (field (name "MPN") "RC0603FR-0710KL"))
      (libsource (lib "eagle-import") (part "R-EU_R060310K"))
    )
    (comp (ref "R9")
      (value "10k")
      (footprint "eagle-import:R0603")
      (fields (field (name "MF") "Yageo") (field (name "MPN") "RC0603FR-0710KL"))
      (libsource (lib "eagle-import") (part "R-EU_R060310K"))
    )
    (comp (ref "R22")
      (value "180k")
      (footprint "eagle-import:R0603")
      (fields
        (field (name "MF") "Yageo")
        (field (name "MPN") "AC0603FR-07180KL")
        (field (name "VALUE_PART") "180K")
      )
      (libsource (lib "eagle-import") (part "R-EU_R0603180K"))
    )
    (comp (ref "R25")
      (value "180k")
      (footprint "eagle-import:R0603")
      (fields
        (field (name "MF") "Yageo")
        (field (name "MPN") "AC0603FR-07180KL")
        (field (name "VALUE_PART") "180K")
        (field (name "DIGIKEY") "311-180KLDCT-ND")
        (field (name "MPN_1") "AC0603FR-07180KL")
        (field (name "VALUE_PART_1") "180k")
      )
      (libsource (lib "eagle-import") (part "R-EU_R0603180K"))
    )
    (comp (ref "R42")
      (value "10k")
      (footprint "eagle-import:R0603")
      (libsource (lib "eagle-import") (part "rcl_334_R-EU_R0603"))
    )
    (comp (ref "R43")
      (value "10k")
      (footprint "eagle-import:R0603")
      (fields (field (name "MF") "Yageo") (field (name "MPN") "RC0603FR-0710KL"))
      (libsource (lib "eagle-import") (part "R-EU_R060310K"))
    )
    (comp (ref "U$7")
      (value "LTC2495")
      (footprint "eagle-import:QFN38-5X7")
      (fields (field (name "MF") "LT") (field (name "MPN") "LTC2495IUHF#PBF"))
      (libsource (lib "eagle-import") (part "LTC2495"))
    )
  )
  (nets
    (net (code "1") (name "+3V3") (class "Default")
      (node (ref "ADECOUP") (pin "1") (pinfunction "1_1") (pintype "passive"))
      (node (ref "C10") (pin "1") (pinfunction "1_1") (pintype "passive"))
      (node (ref "C5") (pin "1") (pinfunction "1_1") (pintype "passive"))
      (node (ref "IC2") (pin "17") (pinfunction "VCC_17") (pintype "power_in"))
      (node (ref "IC2") (pin "27") (pinfunction "AVCC_27") (pintype "power_in"))
      (node (ref "IC2") (pin "29") (pinfunction "AREF_29") (pintype "passive"))
      (node (ref "IC2") (pin "38") (pinfunction "VCC_38") (pintype "power_in"))
      (node (ref "IC2") (pin "5") (pinfunction "VCC_5") (pintype "power_in"))
      (node (ref "ISP2") (pin "2") (pinfunction "VCC_2") (pintype "power_in"))
      (node (ref "L2") (pin "P$2") (pinfunction "2_P$2") (pintype "passive"))
      (node (ref "Q5") (pin "2") (pinfunction "S_2") (pintype "bidirectional"))
      (node (ref "Q7") (pin "2") (pinfunction "S_2") (pintype "bidirectional"))
      (node (ref "Q8") (pin "1") (pinfunction "G_1") (pintype "bidirectional"))
      (node (ref "Q9") (pin "1") (pinfunction "G_1") (pintype "bidirectional"))
      (node (ref "R1") (pin "2") (pinfunction "2_2") (pintype "passive"))
      (node (ref "R42") (pin "2") (pinfunction "2_2") (pintype "passive"))
      (node (ref "R43") (pin "2") (pinfunction "2_2") (pintype "passive"))
      (node (ref "U$2") (pin "4") (pinfunction "VIN_4") (pintype "bidirectional"))
      (node (ref "U$3") (pin "6") (pinfunction "VOS_6") (pintype "bidirectional"))
      (node (ref "U$7") (pin "22") (pinfunction "CH14_22") (pintype "input"))
    )
    (net (code "2") (name "+5V") (class "Default")
      (node (ref "C1") (pin "1") (pinfunction "1_1") (pintype "passive"))
      (node (ref "C18") (pin "1") (pinfunction "1_1") (pintype "passive"))
      (node (ref "C2") (pin "1") (pinfunction "1_1") (pintype "passive"))
      (node (ref "C24") (pin "1") (pinfunction "1_1") (pintype "passive"))
      (node (ref "C4") (pin "1") (pinfunction "1_1") (pintype "passive"))
      (node (ref "Q10") (pin "2") (pinfunction "S_2") (pintype "bidirectional"))
      (node (ref "Q12") (pin "2") (pinfunction "S_2") (pintype "bidirectional"))
      (node (ref "R14") (pin "1") (pinfunction "1_1") (pintype "passive"))
      (node (ref "R16") (pin "2") (pinfunction "2_2") (pintype "passive"))
      (node (ref "R8") (pin "2") (pinfunction "2_2") (pintype "passive"))
      (node (ref "R9") (pin "2") (pinfunction "2_2") (pintype "passive"))
      (node (ref "U$1") (pin "5") (pinfunction "VDD_5") (pintype "power_in"))
      (node (ref "U$12") (pin "5") (pinfunction "VDD_5") (pintype "power_in"))
      (node (ref "U$16") (pin "5") (pinfunction "VDD_5") (pintype "power_in"))
      (node (ref "U$3") (pin "2") (pinfunction "VIN_2") (pintype "bidirectional"))
      (node (ref "U$3") (pin "3") (pinfunction "EN_3") (pintype "bidirectional"))
      (node (ref "U$7") (pin "28") (pinfunction "VCC_28") (pintype "power_in"))
      (node (ref "U$7") (pin "29") (pinfunction "REF+_29") (pintype "input"))
      (node (ref "U3") (pin "9") (pinfunction "VOUT_9") (pintype "power_in"))
    )
    (net (code "3") (name "1.8V_EN") (class "Default")
      (node (ref "IC2") (pin "22") (pinfunction "(PCINT19/TMS)PC3_22") (pintype "output"))
      (node (ref "U$2") (pin "3") (pinfunction "EN_3") (pintype "bidirectional"))
    )
    (net (code "4") (name "1.8V_REF") (class "Default")
      (node (ref "C6") (pin "1") (pinfunction "1_1") (pintype "passive"))
      (node (ref "U$2") (pin "5") (pinfunction "OUTS_5") (pintype "bidirectional"))
      (node (ref "U$2") (pin "6") (pinfunction "OUTF_6") (pintype "bidirectional"))
      (node (ref "U$7") (pin "23") (pinfunction "CH15_23") (pintype "input"))
    )
    (net (code "5") (name "3.3V_EXT_CTRL") (class "Default")
      (node (ref "IC2") (pin "35") (pinfunction "(PCINT2/ADC2)PA2_35") (pintype "bidirectional"))
      (node (ref "U$12") (pin "1") (pinfunction "INP_1") (pintype "input"))
    )
    (net (code "6") (name "5V_EXT_CTRL") (class "Default")
      (node (ref "IC2") (pin "34") (pinfunction "(PCINT3/ADC3)PA3_34") (pintype "bidirectional"))
      (node (ref "U$1") (pin "1") (pinfunction "INP_1") (pintype "input"))
    )
    (net (code "7") (name "ADC0") (class "Default")
      (node (ref "C12") (pin "2") (pinfunction "2_2") (pintype "passive"))
      (node (ref "J8") (pin "P$4") (pinfunction "4_P$4") (pintype "passive"))
      (node (ref "R3") (pin "2") (pinfunction "2_2") (pintype "passive"))
      (node (ref "U$7") (pin "8") (pinfunction "CH0_8") (pintype "input"))
    )
    (net (code "8") (name "ADC1") (class "Default")
      (node (ref "C13") (pin "2") (pinfunction "2_2") (pintype "passive"))
      (node (ref "J8") (pin "P$5") (pinfunction "5_P$5") (pintype "passive"))
      (node (ref "R2") (pin "2") (pinfunction "2_2") (pintype "passive"))
      (node (ref "U$7") (pin "9") (pinfunction "CH1_9") (pintype "input"))
    )
    (net (code "9") (name "ADC2") (class "Default")
      (node (ref "C14") (pin "2") (pinfunction "2_2") (pintype "passive"))
      (node (ref "J8") (pin "P$9") (pinfunction "9_P$9") (pintype "passive"))
      (node (ref "R6") (pin "2") (pinfunction "2_2") (pintype "passive"))
      (node (ref "U$7") (pin "10") (pinfunction "CH2_10") (pintype "input"))
    )
    (net (code "10") (name "ADC3") (class "Default")
      (node (ref "C15") (pin "2") (pinfunction "2_2") (pintype "passive"))
      (node (ref "J8") (pin "P$10") (pinfunction "10_P$10") (pintype "passive"))
      (node (ref "R11") (pin "2") (pinfunction "2_2") (pintype "passive"))
      (node (ref "U$7") (pin "11") (pinfunction "CH3_11") (pintype "input"))
    )
    (net (code "11") (name "ADC4") (class "Default")
      (node (ref "C16") (pin "2") (pinfunction "2_2") (pintype "passive"))
      (node (ref "J16") (pin "P$4") (pinfunction "4_P$4") (pintype "passive"))
      (node (ref "R12") (pin "2") (pinfunction "2_2") (pintype "passive"))
      (node (ref "U$7") (pin "12") (pinfunction "CH4_12") (pintype "input"))
    )
    (net (code "12") (name "ADC5") (class "Default")
      (node (ref "C17") (pin "2") (pinfunction "2_2") (pintype "passive"))
      (node (ref "J16") (pin "P$5") (pinfunction "5_P$5") (pintype "passive"))
      (node (ref "R17") (pin "2") (pinfunction "2_2") (pintype "passive"))
      (node (ref "U$7") (pin "13") (pinfunction "CH5_13") (pintype "input"))
    )
    (net (code "13") (name "ADC6") (class "Default")
      (node (ref "C28") (pin "2") (pinfunction "2_2") (pintype "passive"))
      (node (ref "J16") (pin "P$9") (pinfunction "9_P$9") (pintype "passive"))
      (node (ref "R23") (pin "2") (pinfunction "2_2") (pintype "passive"))
      (node (ref "U$7") (pin "14") (pinfunction "CH6_14") (pintype "input"))
    )
    (net (code "14") (name "ADC7") (class "Default")
      (node (ref "C29") (pin "2") (pinfunction "2_2") (pintype "passive"))
      (node (ref "J16") (pin "P$10") (pinfunction "10_P$10") (pintype "passive"))
      (node (ref "R24") (pin "2") (pinfunction "2_2") (pintype "passive"))
      (node (ref "U$7") (pin "15") (pinfunction "CH7_15") (pintype "input"))
    )
    (net (code "15") (name "ADC8") (class "Default")
      (node (ref "C30") (pin "2") (pinfunction "2_2") (pintype "passive"))
      (node (ref "J15") (pin "P$5") (pinfunction "5_P$5") (pintype "passive"))
      (node (ref "U$7") (pin "16") (pinfunction "CH8_16") (pintype "input"))
    )
    (net (code "16") (name "ADC9") (class "Default")
      (node (ref "C31") (pin "2") (pinfunction "2_2") (pintype "passive"))
      (node (ref "J15") (pin "P$4") (pinfunction "4_P$4") (pintype "passive"))
      (node (ref "U$7") (pin "17") (pinfunction "CH9_17") (pintype "input"))
    )
    (net (code "17") (name "ADC10") (class "Default")
      (node (ref "C32") (pin "2") (pinfunction "2_2") (pintype "passive"))
      (node (ref "J14") (pin "P$10") (pinfunction "10_P$10") (pintype "passive"))
      (node (ref "U$7") (pin "18") (pinfunction "CH10_18") (pintype "input"))
    )
    (net (code "18") (name "ADC11") (class "Default")
      (node (ref "C33") (pin "2") (pinfunction "2_2") (pintype "passive"))
      (node (ref "J14") (pin "P$9") (pinfunction "9_P$9") (pintype "passive"))
      (node (ref "U$7") (pin "19") (pinfunction "CH11_19") (pintype "input"))
    )
    (net (code "19") (name "ADC12") (class "Default")
      (node (ref "C34") (pin "2") (pinfunction "2_2") (pintype "passive"))
      (node (ref "J14") (pin "P$5") (pinfunction "5_P$5") (pintype "passive"))
      (node (ref "U$7") (pin "20") (pinfunction "CH12_20") (pintype "input"))
    )
    (net (code "20") (name "ADC13") (class "Default")
      (node (ref "C35") (pin "2") (pinfunction "2_2") (pintype "passive"))
      (node (ref "J14") (pin "P$4") (pinfunction "4_P$4") (pintype "passive"))
      (node (ref "U$7") (pin "21") (pinfunction "CH13_21") (pintype "input"))
    )
    (net (code "21") (name "BATT+") (class "Default")
      (node (ref "C22") (pin "1") (pinfunction "1_1") (pintype "passive"))
      (node (ref "C25") (pin "1") (pinfunction "1_1") (pintype "passive"))
      (node (ref "J2") (pin "P$9") (pinfunction "9_P$9") (pintype "passive"))
      (node (ref "J4") (pin "2") (pinfunction "+_2") (pintype "bidirectional"))
      (node (ref "J6") (pin "VIN0") (pinfunction "PWR_VIN0") (pintype "bidirectional"))
      (node (ref "R18") (pin "2") (pinfunction "2_2") (pintype "passive"))
      (node (ref "U3") (pin "2") (pinfunction "VIN_2") (pintype "power_in"))
      (node (ref "U3") (pin "3") (pinfunction "EN_3") (pintype "input"))
    )
    (net (code "22") (name "D3~{}") (class "Default")
      (node (ref "IC2") (pin "43") (pinfunction "(PCINT11/OC0A/AIN1)PB3_43") (pintype "bidirectional"))
      (node (ref "J2") (pin "P$6") (pinfunction "6_P$6") (pintype "passive"))
    )
    (net (code "23") (name "D12~{}") (class "Default")
      (node (ref "IC2") (pin "13") (pinfunction "(PCINT28/OC1B)PD4_13") (pintype "bidirectional"))
      (node (ref "J1") (pin "P$3") (pinfunction "3_P$3") (pintype "passive"))
    )
    (net (code "24") (name "D13~{}") (class "Default")
      (node (ref "IC2") (pin "14") (pinfunction "(PCINT29/OC1A)PD5_14") (pintype "bidirectional"))
      (node (ref "J1") (pin "P$4") (pinfunction "4_P$4") (pintype "passive"))
    )
    (net (code "25") (name "D14~{}") (class "Default")
      (node (ref "IC2") (pin "15") (pinfunction "(PCINT30/OC2B/ICP)PD6_15") (pintype "bidirectional"))
      (node (ref "J1") (pin "P$8") (pinfunction "8_P$8") (pintype "passive"))
    )
    (net (code "26") (name "D15~{}") (class "Default")
      (node (ref "IC2") (pin "16") (pinfunction "(PCINT31/OC2A)PD7_16") (pintype "bidirectional"))
      (node (ref "J2") (pin "P$8") (pinfunction "8_P$8") (pintype "passive"))
    )
    (net (code "27") (name "D20") (class "Default")
      (node (ref "IC2") (pin "23") (pinfunction "(PCINT20/TDO)PC4_23") (pintype "output"))
    )
    (net (code "28") (name "D22") (class "Default")
      (node (ref "IC2") (pin "25") (pinfunction "(PCINT22/TOSC1)PC6_25") (pintype "output"))
    )
    (net (code "29") (name "DTR") (class "Default")
      (node (ref "C43") (pin "2") (pinfunction "2_2") (pintype "passive"))
      (node (ref "U2") (pin "18") (pinfunction "DTR#_18") (pintype "bidirectional"))
    )
    (net (code "30") (name "EXT_3.3V") (class "Default")
      (node (ref "F1") (pin "2") (pinfunction "2_2") (pintype "bidirectional"))
      (node (ref "J1") (pin "P$6") (pinfunction "6_P$6") (pintype "passive"))
      (node (ref "J14") (pin "P$7") (pinfunction "7_P$7") (pintype "passive"))
      (node (ref "J15") (pin "P$7") (pinfunction "7_P$7") (pintype "passive"))
      (node (ref "J16") (pin "P$7") (pinfunction "7_P$7") (pintype "passive"))
      (node (ref "J2") (pin "P$4") (pinfunction "4_P$4") (pintype "passive"))
      (node (ref "J8") (pin "P$2") (pinfunction "2_P$2") (pintype "passive"))
      (node (ref "J8") (pin "P$7") (pinfunction "7_P$7") (pintype "passive"))
      (node (ref "RTC1") (pin "2") (pinfunction "VCC_2") (pintype "power_in"))
    )
    (net (code "31") (name "EXT_5V") (class "Default")
      (node (ref "F2") (pin "2") (pinfunction "2_2") (pintype "bidirectional"))
      (node (ref "J1") (pin "P$7") (pinfunction "7_P$7") (pintype "passive"))
      (node (ref "J14") (pin "P$3") (pinfunction "3_P$3") (pintype "passive"))
      (node (ref "J14") (pin "P$8") (pinfunction "8_P$8") (pintype "passive"))
      (node (ref "J15") (pin "P$3") (pinfunction "3_P$3") (pintype "passive"))
      (node (ref "J15") (pin "P$8") (pinfunction "8_P$8") (pintype "passive"))
      (node (ref "J16") (pin "P$8") (pinfunction "8_P$8") (pintype "passive"))
      (node (ref "J2") (pin "P$5") (pinfunction "5_P$5") (pintype "passive"))
      (node (ref "J8") (pin "P$3") (pinfunction "3_P$3") (pintype "passive"))
      (node (ref "J8") (pin "P$8") (pinfunction "8_P$8") (pintype "passive"))
      (node (ref "R22") (pin "2") (pinfunction "2_2") (pintype "passive"))
    )
    (net (code "32") (name "GND") (class "Default")
      (node (ref "ADECOUP") (pin "2") (pinfunction "2_2") (pintype "passive"))
      (node (ref "C1") (pin "2") (pinfunction "2_2") (pintype "passive"))
      (node (ref "C10") (pin "2") (pinfunction "2_2") (pintype "passive"))
      (node (ref "C12") (pin "1") (pinfunction "1_1") (pintype "passive"))
      (node (ref "C13") (pin "1") (pinfunction "1_1") (pintype "passive"))
      (node (ref "C14") (pin "1") (pinfunction "1_1") (pintype "passive"))
      (node (ref "C15") (pin "1") (pinfunction "1_1") (pintype "passive"))
      (node (ref "C16") (pin "1") (pinfunction "1_1") (pintype "passive"))
      (node (ref "C17") (pin "1") (pinfunction "1_1") (pintype "passive"))
      (node (ref "C18") (pin "2") (pinfunction "2_2") (pintype "passive"))
      (node (ref "C2") (pin "2") (pinfunction "2_2") (pintype "passive"))
      (node (ref "C21") (pin "2") (pinfunction "2_2") (pintype "passive"))
      (node (ref "C22") (pin "2") (pinfunction "2_2") (pintype "passive"))
      (node (ref "C23") (pin "2") (pinfunction "2_2") (pintype "passive"))
      (node (ref "C24") (pin "2") (pinfunction "2_2") (pintype "passive"))
      (node (ref "C25") (pin "2") (pinfunction "2_2") (pintype "passive"))
      (node (ref "C28") (pin "1") (pinfunction "1_1") (pintype "passive"))
      (node (ref "C29") (pin "1") (pinfunction "1_1") (pintype "passive"))
      (node (ref "C3") (pin "2") (pinfunction "2_2") (pintype "passive"))
      (node (ref "C30") (pin "1") (pinfunction "1_1") (pintype "passive"))
      (node (ref "C31") (pin "1") (pinfunction "1_1") (pintype "passive"))
      (node (ref "C32") (pin "1") (pinfunction "1_1") (pintype "passive"))
      (node (ref "C33") (pin "1") (pinfunction "1_1") (pintype "passive"))
      (node (ref "C34") (pin "1") (pinfunction "1_1") (pintype "passive"))
      (node (ref "C35") (pin "1") (pinfunction "1_1") (pintype "passive"))
      (node (ref "C4") (pin "2") (pinfunction "2_2") (pintype "passive"))
      (node (ref "C40") (pin "2") (pinfunction "2_2") (pintype "passive"))
      (node (ref "C41") (pin "2") (pinfunction "2_2") (pintype "passive"))
      (node (ref "C42") (pin "2") (pinfunction "2_2") (pintype "passive"))
      (node (ref "C5") (pin "2") (pinfunction "2_2") (pintype "passive"))
      (node (ref "C6") (pin "2") (pinfunction "2_2") (pintype "passive"))
      (node (ref "C7") (pin "2") (pinfunction "2_2") (pintype "passive"))
      (node (ref "CLOCK_BATT") (pin "GND") (pinfunction "-_GND") (pintype "passive"))
      (node (ref "CX2") (pin "1") (pinfunction "1_1") (pintype "passive"))
      (node (ref "CX3") (pin "1") (pinfunction "1_1") (pintype "passive"))
      (node (ref "IC2") (pin "18") (pinfunction "GND_18") (pintype "power_in"))
      (node (ref "IC2") (pin "28") (pinfunction "GND_28") (pintype "power_in"))
      (node (ref "IC2") (pin "39") (pinfunction "GND_39") (pintype "power_in"))
      (node (ref "IC2") (pin "6") (pinfunction "GND_6") (pintype "power_in"))
      (node (ref "IC2") (pin "TH") (pinfunction "EXP_TH") (pintype "power_in"))
      (node (ref "ISP2") (pin "6") (pinfunction "GND_6") (pintype "power_in"))
      (node (ref "J1") (pin "P$5") (pinfunction "5_P$5") (pintype "passive"))
      (node (ref "J14") (pin "P$6") (pinfunction "6_P$6") (pintype "passive"))
      (node (ref "J15") (pin "P$6") (pinfunction "6_P$6") (pintype "passive"))
      (node (ref "J16") (pin "P$3") (pinfunction "3_P$3") (pintype "passive"))
      (node (ref "J16") (pin "P$6") (pinfunction "6_P$6") (pintype "passive"))
      (node (ref "J2") (pin "P$10") (pinfunction "10_P$10") (pintype "passive"))
      (node (ref "J2") (pin "P$3") (pinfunction "3_P$3") (pintype "passive"))
      (node (ref "J4") (pin "1") (pinfunction "-_1") (pintype "bidirectional"))
      (node (ref "J6") (pin "GND") (pinfunction "GNDBREAK_GND") (pintype "bidirectional"))
      (node (ref "J6") (pin "P$4") (pinfunction "GND_P$4") (pintype "bidirectional"))
      (node (ref "J8") (pin "P$1") (pinfunction "1_P$1") (pintype "passive"))
      (node (ref "J8") (pin "P$6") (pinfunction "6_P$6") (pintype "passive"))
      (node (ref "LED3") (pin "C") (pinfunction "C_C") (pintype "passive"))
      (node (ref "MICRO_USB") (pin "5") (pinfunction "GND_5") (pintype "power_in"))
      (node (ref "Q11") (pin "2") (pinfunction "S_2") (pintype "bidirectional"))
      (node (ref "R15") (pin "1") (pinfunction "1_1") (pintype "passive"))
      (node (ref "R19") (pin "2") (pinfunction "2_2") (pintype "passive"))
      (node (ref "R20") (pin "1") (pinfunction "1_1") (pintype "passive"))
      (node (ref "R25") (pin "1") (pinfunction "1_1") (pintype "passive"))
      (node (ref "RTC1") (pin "5") (pinfunction "GND_5") (pintype "power_in"))
      (node (ref "S1") (pin "P$3") (pinfunction "3_P$3") (pintype "bidirectional"))
      (node (ref "S1") (pin "P$4") (pinfunction "4_P$4") (pintype "bidirectional"))
      (node (ref "SD") (pin "3") (pinfunction "VSS1_3") (pintype "power_in"))
      (node (ref "SD") (pin "6") (pinfunction "VSS2_6") (pintype "power_in"))
      (node (ref "SD") (pin "GP") (pinfunction "GND_GP") (pintype "power_in"))
      (node (ref "SD") (pin "GP3") (pinfunction "COMMON_SW_GP3") (pintype "passive"))
      (node (ref "SJ1") (pin "1") (pinfunction "1_1") (pintype "passive"))
      (node (ref "SJ2") (pin "1") (pinfunction "1_1") (pintype "passive"))
      (node (ref "U$1") (pin "2") (pinfunction "GND_2") (pintype "power_in"))
      (node (ref "U$12") (pin "2") (pinfunction "GND_2") (pintype "power_in"))
      (node (ref "U$16") (pin "2") (pinfunction "GND_2") (pintype "power_in"))
      (node (ref "U$2") (pin "2") (pinfunction "GND_2") (pintype "bidirectional"))
      (node (ref "U$3") (pin "1") (pinfunction "PGND_1") (pintype "bidirectional"))
      (node (ref "U$3") (pin "4") (pinfunction "AGND_4") (pintype "bidirectional"))
      (node (ref "U$3") (pin "5") (pinfunction "FB_5") (pintype "bidirectional"))
      (node (ref "U$3") (pin "PAD") (pinfunction "PAD_PAD") (pintype "bidirectional"))
      (node (ref "U$4") (pin "P$1") (pinfunction "1_P$1") (pintype "bidirectional"))
      (node (ref "U$4") (pin "P$2") (pinfunction "2_P$2") (pintype "bidirectional"))
      (node (ref "U$7") (pin "1") (pinfunction "GND_1") (pintype "power_in"))
      (node (ref "U$7") (pin "30") (pinfunction "REF-_30") (pintype "input"))
      (node (ref "U$7") (pin "31") (pinfunction "GND_31") (pintype "power_in"))
      (node (ref "U$7") (pin "32") (pinfunction "GND_32") (pintype "power_in"))
      (node (ref "U$7") (pin "33") (pinfunction "GND_33") (pintype "power_in"))
      (node (ref "U$7") (pin "34") (pinfunction "GND_34") (pintype "power_in"))
      (node (ref "U$7") (pin "4") (pinfunction "GND_4") (pintype "power_in"))
      (node (ref "U$7") (pin "6") (pinfunction "GND_6") (pintype "power_in"))
      (node (ref "U$7") (pin "EXP") (pinfunction "GND_EXP") (pintype "power_in"))
      (node (ref "U2") (pin "13") (pinfunction "GND_13") (pintype "bidirectional"))
      (node (ref "U2") (pin "21") (pinfunction "GND_21") (pintype "bidirectional"))
      (node (ref "U2") (pin "3") (pinfunction "GND_3") (pintype "bidirectional"))
      (node (ref "U2") (pin "6") (pinfunction "CTS#_6") (pintype "bidirectional"))
      (node (ref "U3") (pin "7") (pinfunction "GND_7") (pintype "power_in"))
      (node (ref "U3") (pin "THERMAL@1") (pinfunction "PGND_THERMAL@1") (pintype "power_in"))
      (node (ref "U3") (pin "THERMAL@10") (pinfunction "PGND_THERMAL@10") (pintype "power_in"))
      (node (ref "U3") (pin "THERMAL@11") (pinfunction "PGND_THERMAL@11") (pintype "power_in"))
      (node (ref "U3") (pin "THERMAL@12") (pinfunction "PGND_THERMAL@12") (pintype "power_in"))
      (node (ref "U3") (pin "THERMAL@13") (pinfunction "PGND_THERMAL@13") (pintype "power_in"))
      (node (ref "U3") (pin "THERMAL@14") (pinfunction "PGND_THERMAL@14") (pintype "power_in"))
      (node (ref "U3") (pin "THERMAL@5") (pinfunction "PGND_THERMAL@5") (pintype "power_in"))
      (node (ref "U3") (pin "THERMAL@6") (pinfunction "PGND_THERMAL@6") (pintype "power_in"))
      (node (ref "U3") (pin "THERMAL@7") (pinfunction "PGND_THERMAL@7") (pintype "power_in"))
      (node (ref "U3") (pin "THERMAL@8") (pinfunction "PGND_THERMAL@8") (pintype "power_in"))
      (node (ref "U3") (pin "THERMAL@9") (pinfunction "PGND_THERMAL@9") (pintype "power_in"))
    )
    (net (code "33") (name "MANUAL_LOG") (class "Default")
      (node (ref "D1") (pin "2") (pinfunction "A2_2") (pintype "passive"))
      (node (ref "IC2") (pin "26") (pinfunction "(PCINT23/TOSC2)PC7_26") (pintype "output"))
    )
    (net (code "34") (name "MCU_ADC0") (class "Default")
      (node (ref "IC2") (pin "37") (pinfunction "(PCINT0/ADC0)PA0_37") (pintype "bidirectional"))
      (node (ref "J2") (pin "P$7") (pinfunction "7_P$7") (pintype "passive"))
    )
    (net (code "35") (name "MCU_ADC1") (class "Default")
      (node (ref "IC2") (pin "36") (pinfunction "(PCINT1/ADC1)PA1_36") (pintype "bidirectional"))
    )
    (net (code "36") (name "MCU_ADC4") (class "Default")
      (node (ref "IC2") (pin "33") (pinfunction "(PCINT4/ADC4)PA4_33") (pintype "bidirectional"))
    )
    (net (code "37") (name "MCU_ADC5") (class "Default")
      (node (ref "IC2") (pin "32") (pinfunction "(PCINT5/ADC5)PA5_32") (pintype "bidirectional"))
    )
    (net (code "38") (name "MCU_ADC6") (class "Default")
      (node (ref "IC2") (pin "31") (pinfunction "(PCINT6/ADC6)PA6_31") (pintype "bidirectional"))
    )
    (net (code "39") (name "MISO{slash}D6") (class "Default")
      (node (ref "IC2") (pin "2") (pinfunction "(PCINT14/MISO)PB6_2") (pintype "bidirectional"))
      (node (ref "ISP2") (pin "1") (pinfunction "MISO_1") (pintype "input"))
      (node (ref "J15") (pin "P$10") (pinfunction "10_P$10") (pintype "passive"))
      (node (ref "SD") (pin "7") (pinfunction "DATA_OUT_7") (pintype "output"))
    )
    (net (code "40") (name "MOSI{slash}D5") (class "Default")
      (node (ref "IC2") (pin "1") (pinfunction "(PCINT13/MOSI)PB5_1") (pintype "bidirectional"))
      (node (ref "ISP2") (pin "4") (pinfunction "MOSI_4") (pintype "output"))
      (node (ref "J2") (pin "P$1") (pinfunction "1_P$1") (pintype "passive"))
      (node (ref "SD") (pin "2") (pinfunction "DATA_IN_2") (pintype "input"))
    )
    (net (code "41") (name "Net-(D1-K)") (class "Default")
      (node (ref "D1") (pin "3") (pinfunction "K_3") (pintype "passive"))
      (node (ref "S1") (pin "P$1") (pinfunction "1_P$1") (pintype "bidirectional"))
      (node (ref "S1") (pin "P$2") (pinfunction "2_P$2") (pintype "bidirectional"))
    )
    (net (code "42") (name "Net-(IC2-(PCINT7{slash}ADC7)PA7)") (class "Default")
      (node (ref "IC2") (pin "30") (pinfunction "(PCINT7/ADC7)PA7_30") (pintype "bidirectional"))
      (node (ref "R18") (pin "1") (pinfunction "1_1") (pintype "passive"))
      (node (ref "R19") (pin "1") (pinfunction "1_1") (pintype "passive"))
    )
    (net (code "43") (name "Net-(IC2-(PCINT8{slash}XCK0{slash}T0)PB0)") (class "Default")
      (node (ref "IC2") (pin "40") (pinfunction "(PCINT8/XCK0/T0)PB0_40") (pintype "bidirectional"))
      (node (ref "R_LED1") (pin "1") (pinfunction "1_1") (pintype "passive"))
    )
    (net (code "44") (name "Net-(IC2-XTAL1)") (class "Default")
      (node (ref "C42") (pin "1") (pinfunction "1_1") (pintype "passive"))
      (node (ref "IC2") (pin "8") (pinfunction "XTAL1_8") (pintype "bidirectional"))
      (node (ref "Q3") (pin "1") (pinfunction "1_1") (pintype "passive"))
    )
    (net (code "45") (name "Net-(IC2-XTAL2)") (class "Default")
      (node (ref "C41") (pin "1") (pinfunction "1_1") (pintype "passive"))
      (node (ref "IC2") (pin "7") (pinfunction "XTAL2_7") (pintype "bidirectional"))
      (node (ref "Q3") (pin "2") (pinfunction "2_2") (pintype "passive"))
    )
    (net (code "46") (name "Net-(L1-1)") (class "Default")
      (node (ref "L1") (pin "P$1") (pinfunction "1_P$1") (pintype "passive"))
      (node (ref "U3") (pin "1") (pinfunction "L1_1") (pintype "input"))
    )
    (net (code "47") (name "Net-(L1-2)") (class "Default")
      (node (ref "L1") (pin "P$2") (pinfunction "2_P$2") (pintype "passive"))
      (node (ref "U3") (pin "10") (pinfunction "L2_10") (pintype "input"))
    )
    (net (code "48") (name "Net-(L2-1)") (class "Default")
      (node (ref "L2") (pin "P$1") (pinfunction "1_P$1") (pintype "passive"))
      (node (ref "U$3") (pin "7") (pinfunction "SW_7") (pintype "bidirectional"))
    )
    (net (code "49") (name "Net-(LED2-PadA)") (class "Default")
      (node (ref "LED2") (pin "A") (pinfunction "A_A") (pintype "passive"))
      (node (ref "RN1") (pin "1") (pinfunction "1_1") (pintype "passive"))
    )
    (net (code "50") (name "Net-(LED3-PadA)") (class "Default")
      (node (ref "LED3") (pin "A") (pinfunction "A_A") (pintype "passive"))
      (node (ref "R_LED1") (pin "2") (pinfunction "2_2") (pintype "passive"))
    )
    (net (code "51") (name "Net-(MICRO_USB-D+)") (class "Default")
      (node (ref "CX3") (pin "2") (pinfunction "2_2") (pintype "passive"))
      (node (ref "D+") (pin "2") (pinfunction "2_2") (pintype "passive"))
      (node (ref "MICRO_USB") (pin "3") (pinfunction "D+_3") (pintype "bidirectional"))
    )
    (net (code "52") (name "Net-(MICRO_USB-D-)") (class "Default")
      (node (ref "CX2") (pin "2") (pinfunction "2_2") (pintype "passive"))
      (node (ref "D-") (pin "2") (pinfunction "2_2") (pintype "passive"))
      (node (ref "MICRO_USB") (pin "2") (pinfunction "D-_2") (pintype "bidirectional"))
    )
    (net (code "53") (name "Net-(Q5-D)") (class "Default")
      (node (ref "F1") (pin "1") (pinfunction "1_1") (pintype "bidirectional"))
      (node (ref "Q5") (pin "3") (pinfunction "D_3") (pintype "bidirectional"))
    )
    (net (code "54") (name "Net-(Q5-G)") (class "Default")
      (node (ref "Q5") (pin "1") (pinfunction "G_1") (pintype "bidirectional"))
      (node (ref "U$12") (pin "4") (pinfunction "OUT_4") (pintype "output"))
    )
    (net (code "55") (name "Net-(Q7-G)") (class "Default")
      (node (ref "Q7") (pin "1") (pinfunction "G_1") (pintype "bidirectional"))
      (node (ref "U$16") (pin "4") (pinfunction "OUT_4") (pintype "output"))
    )
    (net (code "56") (name "Net-(Q10-D)") (class "Default")
      (node (ref "F2") (pin "1") (pinfunction "1_1") (pintype "bidirectional"))
      (node (ref "Q10") (pin "3") (pinfunction "D_3") (pintype "bidirectional"))
    )
    (net (code "57") (name "Net-(Q10-G)") (class "Default")
      (node (ref "Q10") (pin "1") (pinfunction "G_1") (pintype "bidirectional"))
      (node (ref "U$1") (pin "4") (pinfunction "OUT_4") (pintype "output"))
    )
    (net (code "58") (name "Net-(Q11-D)") (class "Default")
      (node (ref "Q11") (pin "3") (pinfunction "D_3") (pintype "bidirectional"))
      (node (ref "Q12") (pin "1") (pinfunction "G_1") (pintype "bidirectional"))
      (node (ref "R14") (pin "2") (pinfunction "2_2") (pintype "passive"))
    )
    (net (code "59") (name "Net-(R11-Pad1)") (class "Default")
      (node (ref "R11") (pin "1") (pinfunction "1_1") (pintype "passive"))
      (node (ref "R2") (pin "1") (pinfunction "1_1") (pintype "passive"))
      (node (ref "R3") (pin "1") (pinfunction "1_1") (pintype "passive"))
      (node (ref "R6") (pin "1") (pinfunction "1_1") (pintype "passive"))
      (node (ref "SJ1") (pin "2") (pinfunction "2_2") (pintype "passive"))
    )
    (net (code "60") (name "Net-(R12-Pad1)") (class "Default")
      (node (ref "R12") (pin "1") (pinfunction "1_1") (pintype "passive"))
      (node (ref "R17") (pin "1") (pinfunction "1_1") (pintype "passive"))
      (node (ref "R23") (pin "1") (pinfunction "1_1") (pintype "passive"))
      (node (ref "R24") (pin "1") (pinfunction "1_1") (pintype "passive"))
      (node (ref "SJ2") (pin "2") (pinfunction "2_2") (pintype "passive"))
    )
    (net (code "61") (name "Net-(RN1B-1)") (class "Default")
      (node (ref "RN1") (pin "2") (pinfunction "1_2") (pintype "passive"))
      (node (ref "U2") (pin "1") (pinfunction "RXD_1") (pintype "bidirectional"))
    )
    (net (code "62") (name "Net-(RN1C-1)") (class "Default")
      (node (ref "RN1") (pin "3") (pinfunction "1_3") (pintype "passive"))
      (node (ref "U2") (pin "17") (pinfunction "TXD_17") (pintype "bidirectional"))
    )
    (net (code "63") (name "Net-(RN1D-1)") (class "Default")
      (node (ref "LED1") (pin "A") (pinfunction "A_A") (pintype "passive"))
      (node (ref "RN1") (pin "4") (pinfunction "1_4") (pintype "passive"))
    )
    (net (code "64") (name "Net-(RTC1-VBAT)") (class "Default")
      (node (ref "C7") (pin "1") (pinfunction "1_1") (pintype "passive"))
      (node (ref "CLOCK_BATT") (pin "POWER0") (pinfunction "+_POWER0") (pintype "passive"))
      (node (ref "CLOCK_BATT") (pin "POWER1") (pinfunction "+_POWER1") (pintype "passive"))
      (node (ref "RTC1") (pin "6") (pinfunction "VBAT_6") (pintype "power_in"))
    )
    (net (code "65") (name "Net-(U$2-FILT)") (class "Default")
      (node (ref "C3") (pin "1") (pinfunction "1_1") (pintype "passive"))
      (node (ref "U$2") (pin "1") (pinfunction "FILT_1") (pintype "bidirectional"))
    )
    (net (code "66") (name "Net-(U$7-ADCINN)") (class "Default")
      (node (ref "U$7") (pin "26") (pinfunction "ADCINN_26") (pintype "bidirectional"))
      (node (ref "U$7") (pin "27") (pinfunction "MUXOUTN_27") (pintype "bidirectional"))
    )
    (net (code "67") (name "Net-(U$7-ADCINP)") (class "Default")
      (node (ref "U$7") (pin "24") (pinfunction "MUXOUTP_24") (pintype "bidirectional"))
      (node (ref "U$7") (pin "25") (pinfunction "ADCINP_25") (pintype "bidirectional"))
    )
    (net (code "68") (name "Net-(U$7-COM)") (class "Default")
      (node (ref "R22") (pin "1") (pinfunction "1_1") (pintype "passive"))
      (node (ref "R25") (pin "2") (pinfunction "2_2") (pintype "passive"))
      (node (ref "U$7") (pin "7") (pinfunction "COM_7") (pintype "input"))
    )
    (net (code "69") (name "Net-(U2-3V3OUT)") (class "Default")
      (node (ref "C40") (pin "1") (pinfunction "1_1") (pintype "passive"))
      (node (ref "U2") (pin "10") (pinfunction "3V3OUT_10") (pintype "bidirectional"))
      (node (ref "U2") (pin "11") (pinfunction "RESET#_11") (pintype "bidirectional"))
      (node (ref "U2") (pin "20") (pinfunction "VCCIO_20") (pintype "bidirectional"))
    )
    (net (code "70") (name "Net-(U2-CBUS1)") (class "Default")
      (node (ref "LED1") (pin "C") (pinfunction "C_C") (pintype "passive"))
      (node (ref "U2") (pin "14") (pinfunction "CBUS1_14") (pintype "bidirectional"))
    )
    (net (code "71") (name "Net-(U2-CBUS2)") (class "Default")
      (node (ref "LED2") (pin "C") (pinfunction "C_C") (pintype "passive"))
      (node (ref "U2") (pin "7") (pinfunction "CBUS2_7") (pintype "bidirectional"))
    )
    (net (code "72") (name "Net-(U2-USBDM)") (class "Default")
      (node (ref "D-") (pin "1") (pinfunction "1_1") (pintype "passive"))
      (node (ref "U2") (pin "9") (pinfunction "USBDM_9") (pintype "bidirectional"))
    )
    (net (code "73") (name "Net-(U2-USBDP)") (class "Default")
      (node (ref "D+") (pin "1") (pinfunction "1_1") (pintype "passive"))
      (node (ref "U2") (pin "8") (pinfunction "USBDP_8") (pintype "bidirectional"))
    )
    (net (code "74") (name "Net-(U3-FB)") (class "Default")
      (node (ref "C23") (pin "1") (pinfunction "1_1") (pintype "passive"))
      (node (ref "R15") (pin "2") (pinfunction "2_2") (pintype "passive"))
      (node (ref "R16") (pin "1") (pinfunction "1_1") (pintype "passive"))
      (node (ref "U3") (pin "8") (pinfunction "FB_8") (pintype "input"))
    )
    (net (code "75") (name "Net-(U3-VAUX)") (class "Default")
      (node (ref "C21") (pin "1") (pinfunction "1_1") (pintype "passive"))
      (node (ref "U3") (pin "6") (pinfunction "VAUX_6") (pintype "passive"))
    )
    (net (code "76") (name "PSYNC") (class "Default")
      (node (ref "IC2") (pin "41") (pinfunction "(PCINT9/CLKO/T1)PB1_41") (pintype "bidirectional"))
      (node (ref "U3") (pin "4") (pinfunction "PSYNC_4") (pintype "input"))
    )
    (net (code "77") (name "RST") (class "Default")
      (node (ref "C43") (pin "1") (pinfunction "1_1") (pintype "passive"))
      (node (ref "IC2") (pin "4") (pinfunction "RESET_4") (pintype "input"))
      (node (ref "ISP2") (pin "5") (pinfunction "RST_5") (pintype "output"))
      (node (ref "R1") (pin "1") (pinfunction "1_1") (pintype "passive"))
      (node (ref "U$4") (pin "P$3") (pinfunction "3_P$3") (pintype "bidirectional"))
      (node (ref "U$4") (pin "P$4") (pinfunction "4_P$4") (pintype "bidirectional"))
    )
    (net (code "78") (name "RTC_INT") (class "Default")
      (node (ref "D1") (pin "1") (pinfunction "A1_1") (pintype "passive"))
      (node (ref "IC2") (pin "42") (pinfunction "(PCINT10/INT2/AIN0)PB2_42") (pintype "bidirectional"))
      (node (ref "RTC1") (pin "3") (pinfunction "SQW_3") (pintype "output"))
    )
    (net (code "79") (name "RX_USB") (class "Default")
      (node (ref "IC2") (pin "9") (pinfunction "(PCINT24/RXD0)PD0_9") (pintype "bidirectional"))
      (node (ref "RN1") (pin "6") (pinfunction "2_6") (pintype "passive"))
    )
    (net (code "80") (name "RX{slash}INT0") (class "Default")
      (node (ref "IC2") (pin "11") (pinfunction "(PCINT26/INT0)PD2_11") (pintype "bidirectional"))
      (node (ref "J1") (pin "P$1") (pinfunction "1_P$1") (pintype "passive"))
    )
    (net (code "81") (name "SCK{slash}D7") (class "Default")
      (node (ref "IC2") (pin "3") (pinfunction "(PCINT15/SCK)PB7_3") (pintype "bidirectional"))
      (node (ref "ISP2") (pin "3") (pinfunction "SCK_3") (pintype "output"))
      (node (ref "J15") (pin "P$9") (pinfunction "9_P$9") (pintype "passive"))
      (node (ref "SD") (pin "5") (pinfunction "SCLK_5") (pintype "input"))
    )
    (net (code "82") (name "SCL") (class "Default")
      (node (ref "IC2") (pin "19") (pinfunction "(PCINT16/SCL)PC0_19") (pintype "output"))
      (node (ref "J1") (pin "P$9") (pinfunction "9_P$9") (pintype "passive"))
      (node (ref "J14") (pin "P$1") (pinfunction "1_P$1") (pintype "passive"))
      (node (ref "J15") (pin "P$1") (pinfunction "1_P$1") (pintype "passive"))
      (node (ref "J16") (pin "P$1") (pinfunction "1_P$1") (pintype "passive"))
      (node (ref "Q9") (pin "2") (pinfunction "S_2") (pintype "bidirectional"))
      (node (ref "R42") (pin "1") (pinfunction "1_1") (pintype "passive"))
      (node (ref "RTC1") (pin "8") (pinfunction "SCL_8") (pintype "bidirectional"))
    )
    (net (code "83") (name "SCL_HV") (class "Default")
      (node (ref "Q9") (pin "3") (pinfunction "D_3") (pintype "bidirectional"))
      (node (ref "R9") (pin "1") (pinfunction "1_1") (pintype "passive"))
      (node (ref "U$7") (pin "2") (pinfunction "SCL_2") (pintype "bidirectional"))
    )
    (net (code "84") (name "SDA") (class "Default")
      (node (ref "IC2") (pin "20") (pinfunction "(PCINT17/SDA)PC1_20") (pintype "output"))
      (node (ref "J1") (pin "P$10") (pinfunction "10_P$10") (pintype "passive"))
      (node (ref "J14") (pin "P$2") (pinfunction "2_P$2") (pintype "passive"))
      (node (ref "J15") (pin "P$2") (pinfunction "2_P$2") (pintype "passive"))
      (node (ref "J16") (pin "P$2") (pinfunction "2_P$2") (pintype "passive"))
      (node (ref "Q8") (pin "2") (pinfunction "S_2") (pintype "bidirectional"))
      (node (ref "R43") (pin "1") (pinfunction "1_1") (pintype "passive"))
      (node (ref "RTC1") (pin "7") (pinfunction "SDA_7") (pintype "bidirectional"))
    )
    (net (code "85") (name "SDA_HV") (class "Default")
      (node (ref "Q8") (pin "3") (pinfunction "D_3") (pintype "bidirectional"))
      (node (ref "R8") (pin "1") (pinfunction "1_1") (pintype "passive"))
      (node (ref "U$7") (pin "3") (pinfunction "SDA_3") (pintype "bidirectional"))
    )
    (net (code "86") (name "SD_CS") (class "Default")
      (node (ref "IC2") (pin "24") (pinfunction "(PCINT21/TDI)PC5_24") (pintype "output"))
      (node (ref "SD") (pin "1") (pinfunction "CS_1") (pintype "input"))
    )
    (net (code "87") (name "SD_VCC") (class "Default")
      (node (ref "Q7") (pin "3") (pinfunction "D_3") (pintype "bidirectional"))
      (node (ref "SD") (pin "4") (pinfunction "VDD_4") (pintype "power_in"))
    )
    (net (code "88") (name "SD_VCC_CTRL") (class "Default")
      (node (ref "IC2") (pin "21") (pinfunction "(PCINT18/TCK)PC2_21") (pintype "output"))
      (node (ref "U$16") (pin "1") (pinfunction "INP_1") (pintype "input"))
    )
    (net (code "89") (name "SS{slash}D4") (class "Default")
      (node (ref "IC2") (pin "44") (pinfunction "(PCINT12/OC0B/~{SS})PB4_44") (pintype "bidirectional"))
      (node (ref "J2") (pin "P$2") (pinfunction "2_P$2") (pintype "passive"))
    )
    (net (code "90") (name "TX_USB") (class "Default")
      (node (ref "IC2") (pin "10") (pinfunction "(PCINT25/TXD0)PD1_10") (pintype "bidirectional"))
      (node (ref "RN1") (pin "7") (pinfunction "2_7") (pintype "passive"))
    )
    (net (code "91") (name "TX{slash}INT1") (class "Default")
      (node (ref "IC2") (pin "12") (pinfunction "(PCINT27/INT1)PD3_12") (pintype "bidirectional"))
      (node (ref "J1") (pin "P$2") (pinfunction "2_P$2") (pintype "passive"))
    )
    (net (code "92") (name "VUSB") (class "Default")
      (node (ref "MICRO_USB") (pin "1") (pinfunction "VDD_1") (pintype "power_in"))
      (node (ref "Q11") (pin "1") (pinfunction "G_1") (pintype "bidirectional"))
      (node (ref "Q12") (pin "3") (pinfunction "D_3") (pintype "bidirectional"))
      (node (ref "R20") (pin "2") (pinfunction "2_2") (pintype "passive"))
      (node (ref "RN1") (pin "5") (pinfunction "2_5") (pintype "passive"))
      (node (ref "RN1") (pin "8") (pinfunction "2_8") (pintype "passive"))
      (node (ref "U2") (pin "12") (pinfunction "VCC_12") (pintype "bidirectional"))
    )
    (net (code "93") (name "unconnected-(J4-PAD1-PadNC1)") (class "Default")
      (node (ref "J4") (pin "NC1") (pinfunction "PAD1_NC1") (pintype "bidirectional"))
    )
    (net (code "94") (name "unconnected-(J4-PAD2-PadNC2)") (class "Default")
      (node (ref "J4") (pin "NC2") (pinfunction "PAD2_NC2") (pintype "bidirectional"))
    )
    (net (code "95") (name "unconnected-(MICRO_USB-ID-Pad4)") (class "Default")
      (node (ref "MICRO_USB") (pin "4") (pinfunction "ID_4") (pintype "passive"))
    )
    (net (code "96") (name "unconnected-(RTC1-32KHZ-Pad1)") (class "Default")
      (node (ref "RTC1") (pin "1") (pinfunction "32KHZ_1") (pintype "output"))
    )
    (net (code "97") (name "unconnected-(RTC1-RST-Pad4)") (class "Default")
      (node (ref "RTC1") (pin "4") (pinfunction "RST_4") (pintype "bidirectional"))
    )
    (net (code "98") (name "unconnected-(SD-CARD_DETECT-PadCD)") (class "Default")
      (node (ref "SD") (pin "CD") (pinfunction "CARD_DETECT_CD") (pintype "passive"))
    )
    (net (code "99") (name "unconnected-(SD-DAT1-Pad8)") (class "Default")
      (node (ref "SD") (pin "8") (pinfunction "DAT1_8") (pintype "bidirectional"))
    )
    (net (code "100") (name "unconnected-(SD-DAT2-Pad9)") (class "Default")
      (node (ref "SD") (pin "9") (pinfunction "DAT2_9") (pintype "bidirectional"))
    )
    (net (code "101") (name "unconnected-(SD-WRITE_PROTECT-PadWP)") (class "Default")
      (node (ref "SD") (pin "WP") (pinfunction "WRITE_PROTECT_WP") (pintype "passive"))
    )
    (net (code "102") (name "unconnected-(U$3-PG-Pad8)") (class "Default")
      (node (ref "U$3") (pin "8") (pinfunction "PG_8") (pintype "bidirectional"))
    )
    (net (code "103") (name "unconnected-(U$7-CA0-Pad36)") (class "Default")
      (node (ref "U$7") (pin "36") (pinfunction "CA0_36") (pintype "input"))
    )
    (net (code "104") (name "unconnected-(U$7-CA1-Pad37)") (class "Default")
      (node (ref "U$7") (pin "37") (pinfunction "CA1_37") (pintype "input"))
    )
    (net (code "105") (name "unconnected-(U$7-CA2-Pad38)") (class "Default")
      (node (ref "U$7") (pin "38") (pinfunction "CA2_38") (pintype "input"))
    )
    (net (code "106") (name "unconnected-(U$7-F0-Pad35)") (class "Default")
      (node (ref "U$7") (pin "35") (pinfunction "F0_35") (pintype "input"))
    )
    (net (code "107") (name "unconnected-(U2-CBUS0-Pad15)") (class "Default")
      (node (ref "U2") (pin "15") (pinfunction "CBUS0_15") (pintype "bidirectional"))
    )
    (net (code "108") (name "unconnected-(U2-CBUS3-Pad16)") (class "Default")
      (node (ref "U2") (pin "16") (pinfunction "CBUS3_16") (pintype "bidirectional"))
    )
    (net (code "109") (name "unconnected-(U2-DCD#-Pad5)") (class "Default")
      (node (ref "U2") (pin "5") (pinfunction "DCD#_5") (pintype "bidirectional"))
    )
    (net (code "110") (name "unconnected-(U2-DSR#-Pad4)") (class "Default")
      (node (ref "U2") (pin "4") (pinfunction "DSR#_4") (pintype "bidirectional"))
    )
    (net (code "111") (name "unconnected-(U2-RI#-Pad2)") (class "Default")
      (node (ref "U2") (pin "2") (pinfunction "RI#_2") (pintype "bidirectional"))
    )
    (net (code "112") (name "unconnected-(U2-RTS#-Pad19)") (class "Default")
      (node (ref "U2") (pin "19") (pinfunction "RTS#_19") (pintype "bidirectional"))
    )
    (net (code "113") (name "unconnected-(U3-PG-Pad5)") (class "Default")
      (node (ref "U3") (pin "5") (pinfunction "PG_5") (pintype "open_collector"))
    )
  )
)
